# tarjeta-v10.net
KiCad netlist of a schematic drawn in EAGLE
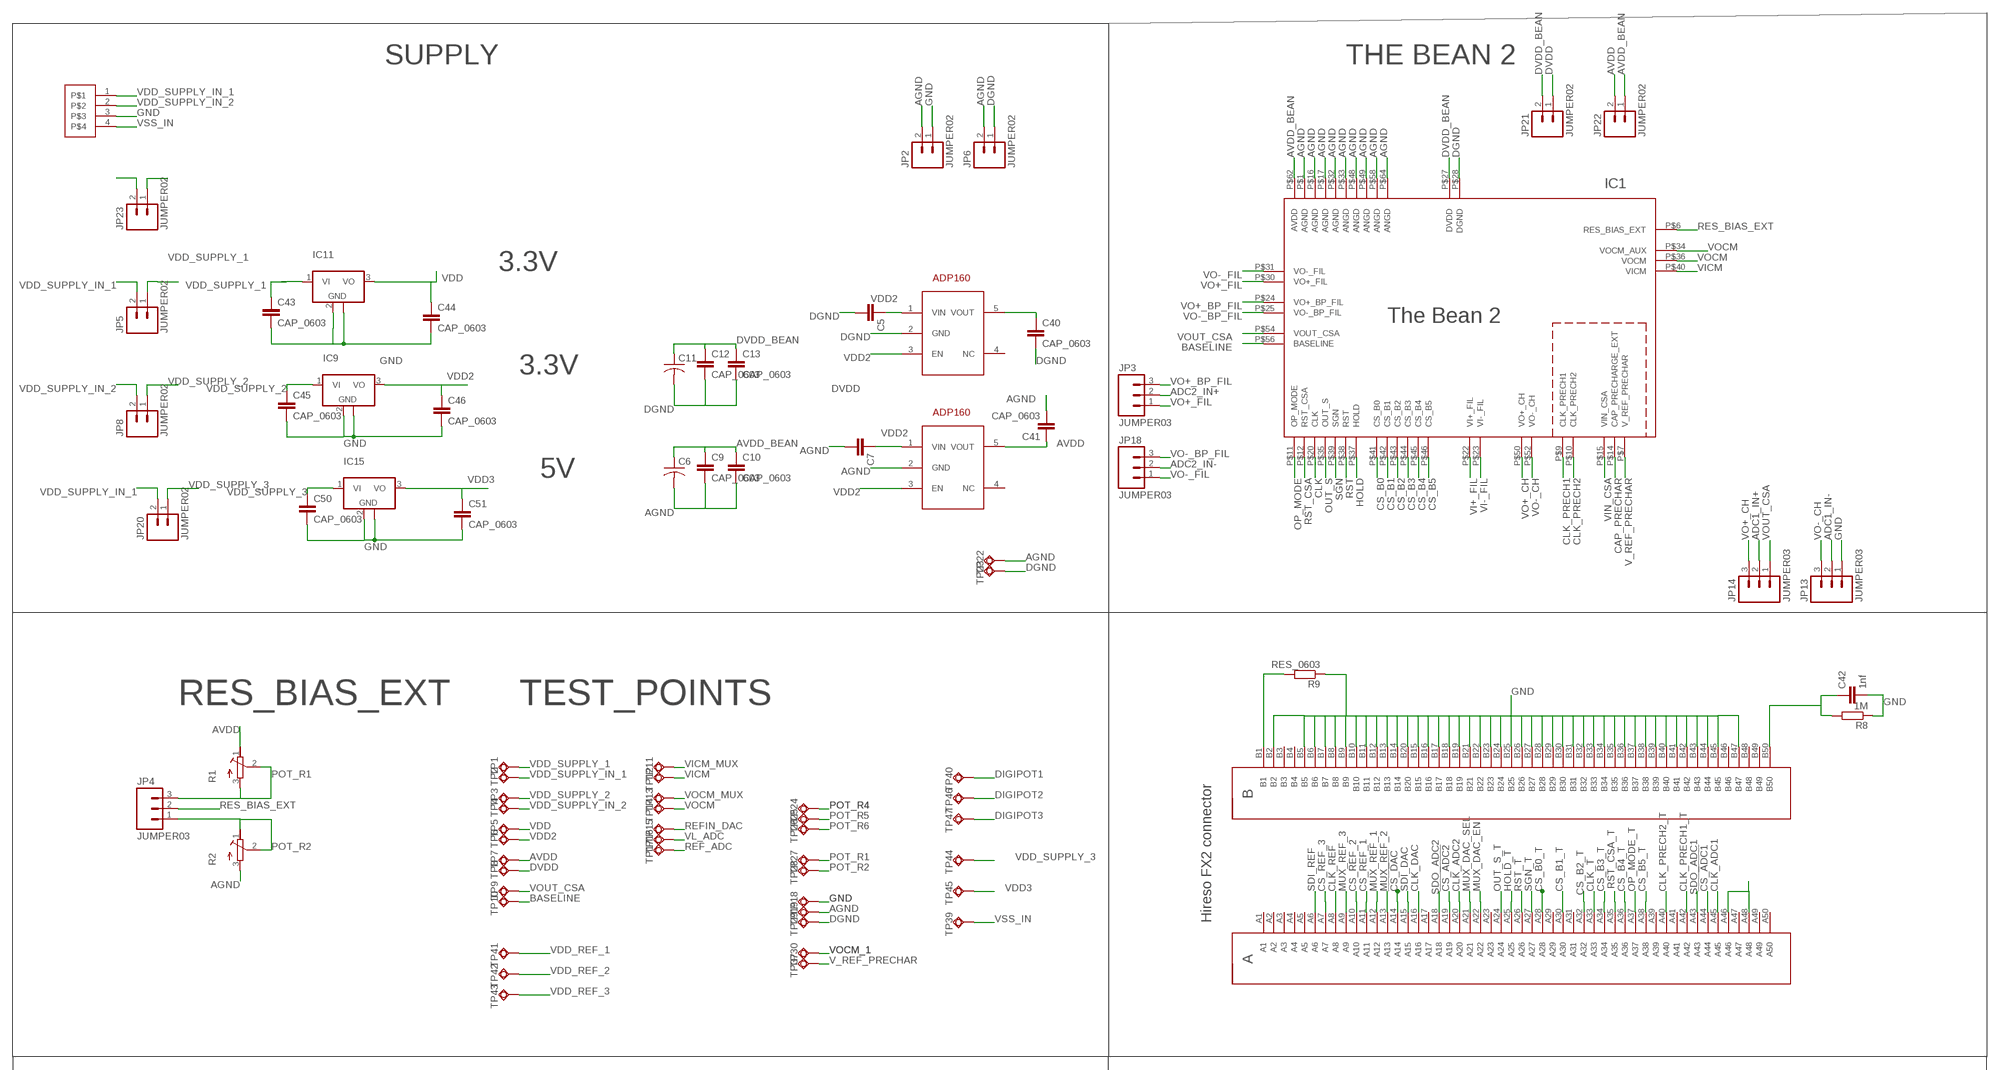
[diagram p0: schematic, sheet 1, part 1 of 3]
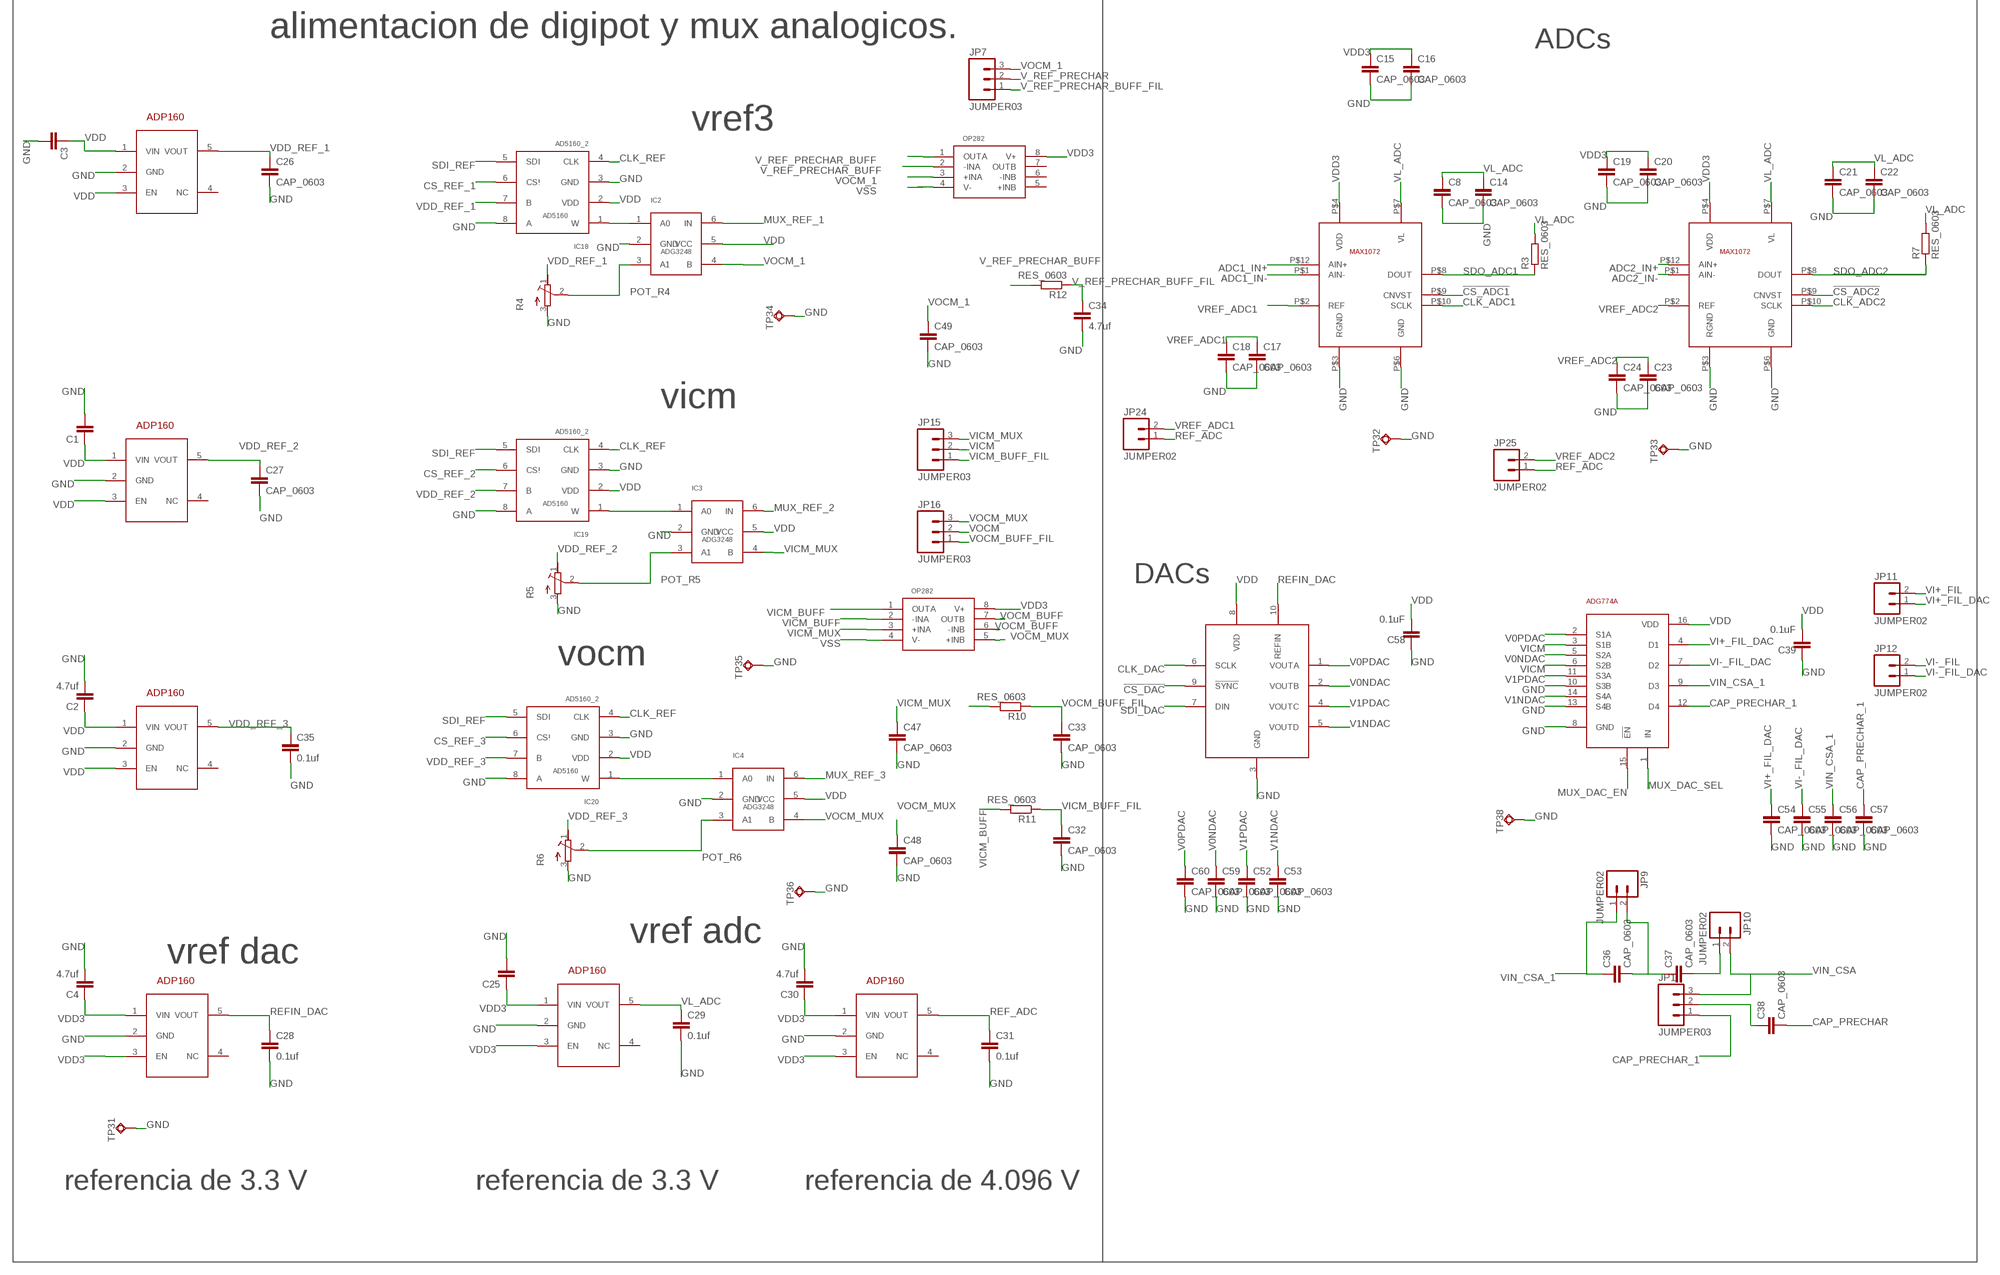
[diagram p1: schematic, sheet 1, part 2 of 3]
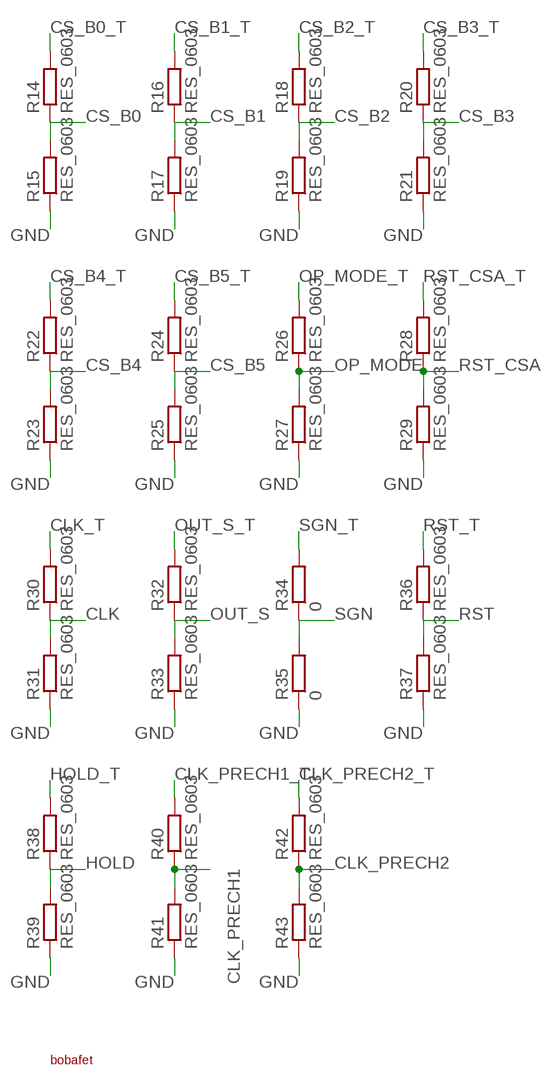
[diagram p2: schematic, sheet 1, part 3 of 3]

(export (version "E")
  (design (tool "Eeschema 10.0.6"))
  (components
    (comp (ref "C1")
      (value "CAP_0402")
      (footprint "eagle-import:C0402")
      (libsource (lib "eagle-import") (part "CAP_0402"))
    )
    (comp (ref "C2")
      (value "4.7uf")
      (footprint "eagle-import:C0402")
      (libsource (lib "eagle-import") (part "CAP_0402"))
    )
    (comp (ref "C3")
      (value "CAP_0402")
      (footprint "eagle-import:C0402")
      (libsource (lib "eagle-import") (part "CAP_0402"))
    )
    (comp (ref "C4")
      (value "4.7uf")
      (footprint "eagle-import:C0402")
      (libsource (lib "eagle-import") (part "CAP_0402"))
    )
    (comp (ref "C5")
      (value "CAP_0402")
      (footprint "eagle-import:C0402")
      (libsource (lib "eagle-import") (part "CAP_0402"))
    )
    (comp (ref "C6")
      (value "CAP_0805")
      (footprint "eagle-import:C0805")
      (libsource (lib "eagle-import") (part "CAP_0805"))
    )
    (comp (ref "C7")
      (value "CAP_0402")
      (footprint "eagle-import:C0402")
      (libsource (lib "eagle-import") (part "CAP_0402"))
    )
    (comp (ref "C8")
      (value "CAP_0603")
      (footprint "eagle-import:C0603")
      (libsource (lib "eagle-import") (part "CAP_0603"))
    )
    (comp (ref "C9")
      (value "CAP_0603")
      (footprint "eagle-import:C0603")
      (libsource (lib "eagle-import") (part "CAP_0603"))
    )
    (comp (ref "C10")
      (value "CAP_0603")
      (footprint "eagle-import:C0603")
      (libsource (lib "eagle-import") (part "CAP_0603"))
    )
    (comp (ref "C11")
      (value "CAP_0805")
      (footprint "eagle-import:C0805")
      (libsource (lib "eagle-import") (part "CAP_0805"))
    )
    (comp (ref "C12")
      (value "CAP_0603")
      (footprint "eagle-import:C0603")
      (libsource (lib "eagle-import") (part "CAP_0603"))
    )
    (comp (ref "C13")
      (value "CAP_0603")
      (footprint "eagle-import:C0603")
      (libsource (lib "eagle-import") (part "CAP_0603"))
    )
    (comp (ref "C14")
      (value "CAP_0603")
      (footprint "eagle-import:C0603")
      (libsource (lib "eagle-import") (part "CAP_0603"))
    )
    (comp (ref "C15")
      (value "CAP_0603")
      (footprint "eagle-import:C0603")
      (libsource (lib "eagle-import") (part "CAP_0603"))
    )
    (comp (ref "C16")
      (value "CAP_0603")
      (footprint "eagle-import:C0603")
      (libsource (lib "eagle-import") (part "CAP_0603"))
    )
    (comp (ref "C17")
      (value "CAP_0603")
      (footprint "eagle-import:C0603")
      (libsource (lib "eagle-import") (part "CAP_0603"))
    )
    (comp (ref "C18")
      (value "CAP_0603")
      (footprint "eagle-import:C0603")
      (libsource (lib "eagle-import") (part "CAP_0603"))
    )
    (comp (ref "C19")
      (value "CAP_0603")
      (footprint "eagle-import:C0603")
      (libsource (lib "eagle-import") (part "CAP_0603"))
    )
    (comp (ref "C20")
      (value "CAP_0603")
      (footprint "eagle-import:C0603")
      (libsource (lib "eagle-import") (part "CAP_0603"))
    )
    (comp (ref "C21")
      (value "CAP_0603")
      (footprint "eagle-import:C0603")
      (libsource (lib "eagle-import") (part "CAP_0603"))
    )
    (comp (ref "C22")
      (value "CAP_0603")
      (footprint "eagle-import:C0603")
      (libsource (lib "eagle-import") (part "CAP_0603"))
    )
    (comp (ref "C23")
      (value "CAP_0603")
      (footprint "eagle-import:C0603")
      (libsource (lib "eagle-import") (part "CAP_0603"))
    )
    (comp (ref "C24")
      (value "CAP_0603")
      (footprint "eagle-import:C0603")
      (libsource (lib "eagle-import") (part "CAP_0603"))
    )
    (comp (ref "C25")
      (value "CAP_0402")
      (footprint "eagle-import:C0402")
      (libsource (lib "eagle-import") (part "CAP_0402"))
    )
    (comp (ref "C26")
      (value "CAP_0603")
      (footprint "eagle-import:C0603")
      (libsource (lib "eagle-import") (part "CAP_0603"))
    )
    (comp (ref "C27")
      (value "CAP_0603")
      (footprint "eagle-import:C0603")
      (libsource (lib "eagle-import") (part "CAP_0603"))
    )
    (comp (ref "C28")
      (value "0.1uf")
      (footprint "eagle-import:C0603")
      (libsource (lib "eagle-import") (part "CAP_0603"))
    )
    (comp (ref "C29")
      (value "0.1uf")
      (footprint "eagle-import:C0603")
      (libsource (lib "eagle-import") (part "CAP_0603"))
    )
    (comp (ref "C30")
      (value "4.7uf")
      (footprint "eagle-import:C0402")
      (libsource (lib "eagle-import") (part "CAP_0402"))
    )
    (comp (ref "C31")
      (value "0.1uf")
      (footprint "eagle-import:C0603")
      (libsource (lib "eagle-import") (part "CAP_0603"))
    )
    (comp (ref "C32")
      (value "CAP_0603")
      (footprint "eagle-import:C0603")
      (libsource (lib "eagle-import") (part "CAP_0603"))
    )
    (comp (ref "C33")
      (value "CAP_0603")
      (footprint "eagle-import:C0603")
      (libsource (lib "eagle-import") (part "CAP_0603"))
    )
    (comp (ref "C34")
      (value "4.7uf")
      (footprint "eagle-import:C0603")
      (libsource (lib "eagle-import") (part "CAP_0603"))
    )
    (comp (ref "C35")
      (value "0.1uf")
      (footprint "eagle-import:C0603")
      (libsource (lib "eagle-import") (part "CAP_0603"))
    )
    (comp (ref "C36")
      (value "CAP_0603")
      (footprint "eagle-import:C0603")
      (libsource (lib "eagle-import") (part "CAP_0603"))
    )
    (comp (ref "C37")
      (value "CAP_0603")
      (footprint "eagle-import:C0603")
      (libsource (lib "eagle-import") (part "CAP_0603"))
    )
    (comp (ref "C38")
      (value "CAP_0603")
      (footprint "eagle-import:C0603")
      (libsource (lib "eagle-import") (part "CAP_0603"))
    )
    (comp (ref "C39")
      (value "0.1uF")
      (footprint "eagle-import:C0603")
      (libsource (lib "eagle-import") (part "CAP_0603"))
    )
    (comp (ref "C40")
      (value "CAP_0603")
      (footprint "eagle-import:C0603")
      (libsource (lib "eagle-import") (part "CAP_0603"))
    )
    (comp (ref "C41")
      (value "CAP_0603")
      (footprint "eagle-import:C0603")
      (libsource (lib "eagle-import") (part "CAP_0603"))
    )
    (comp (ref "C42")
      (value "1nf")
      (footprint "eagle-import:C0603")
      (libsource (lib "eagle-import") (part "CAP_0603"))
    )
    (comp (ref "C43")
      (value "CAP_0603")
      (footprint "eagle-import:C0603")
      (libsource (lib "eagle-import") (part "CAP_0603"))
    )
    (comp (ref "C44")
      (value "CAP_0603")
      (footprint "eagle-import:C0603")
      (libsource (lib "eagle-import") (part "CAP_0603"))
    )
    (comp (ref "C45")
      (value "CAP_0603")
      (footprint "eagle-import:C0603")
      (libsource (lib "eagle-import") (part "CAP_0603"))
    )
    (comp (ref "C46")
      (value "CAP_0603")
      (footprint "eagle-import:C0603")
      (libsource (lib "eagle-import") (part "CAP_0603"))
    )
    (comp (ref "C47")
      (value "CAP_0603")
      (footprint "eagle-import:C0603")
      (libsource (lib "eagle-import") (part "CAP_0603"))
    )
    (comp (ref "C48")
      (value "CAP_0603")
      (footprint "eagle-import:C0603")
      (libsource (lib "eagle-import") (part "CAP_0603"))
    )
    (comp (ref "C49")
      (value "CAP_0603")
      (footprint "eagle-import:C0603")
      (libsource (lib "eagle-import") (part "CAP_0603"))
    )
    (comp (ref "C50")
      (value "CAP_0603")
      (footprint "eagle-import:C0603")
      (libsource (lib "eagle-import") (part "CAP_0603"))
    )
    (comp (ref "C51")
      (value "CAP_0603")
      (footprint "eagle-import:C0603")
      (libsource (lib "eagle-import") (part "CAP_0603"))
    )
    (comp (ref "C52")
      (value "CAP_0603")
      (footprint "eagle-import:C0603")
      (libsource (lib "eagle-import") (part "CAP_0603"))
    )
    (comp (ref "C53")
      (value "CAP_0603")
      (footprint "eagle-import:C0603")
      (libsource (lib "eagle-import") (part "CAP_0603"))
    )
    (comp (ref "C54")
      (value "CAP_0603")
      (footprint "eagle-import:C0603")
      (libsource (lib "eagle-import") (part "CAP_0603"))
    )
    (comp (ref "C55")
      (value "CAP_0603")
      (footprint "eagle-import:C0603")
      (libsource (lib "eagle-import") (part "CAP_0603"))
    )
    (comp (ref "C56")
      (value "CAP_0603")
      (footprint "eagle-import:C0603")
      (libsource (lib "eagle-import") (part "CAP_0603"))
    )
    (comp (ref "C57")
      (value "CAP_0603")
      (footprint "eagle-import:C0603")
      (libsource (lib "eagle-import") (part "CAP_0603"))
    )
    (comp (ref "C58")
      (value "0.1uF")
      (footprint "eagle-import:C0603")
      (libsource (lib "eagle-import") (part "CAP_0603"))
    )
    (comp (ref "C59")
      (value "CAP_0603")
      (footprint "eagle-import:C0603")
      (libsource (lib "eagle-import") (part "CAP_0603"))
    )
    (comp (ref "C60")
      (value "CAP_0603")
      (footprint "eagle-import:C0603")
      (libsource (lib "eagle-import") (part "CAP_0603"))
    )
    (comp (ref "IC1")
      (value "THEBEAN2")
      (footprint "eagle-import:CQFP64")
      (libsource (lib "eagle-import") (part "THEBEAN2"))
    )
    (comp (ref "IC2")
      (value "ADG3248")
      (footprint "eagle-import:SC70")
      (libsource (lib "eagle-import") (part "ADG3248"))
    )
    (comp (ref "IC3")
      (value "ADG3248")
      (footprint "eagle-import:SC70")
      (libsource (lib "eagle-import") (part "ADG3248"))
    )
    (comp (ref "IC4")
      (value "ADG3248")
      (footprint "eagle-import:SC70")
      (libsource (lib "eagle-import") (part "ADG3248"))
    )
    (comp (ref "IC5")
      (value "ADP160")
      (footprint "eagle-import:SOT23-5L_2")
      (libsource (lib "eagle-import") (part "ADP160"))
    )
    (comp (ref "IC6")
      (value "ADP160")
      (footprint "eagle-import:SOT23-5L_2")
      (libsource (lib "eagle-import") (part "ADP160"))
    )
    (comp (ref "IC7")
      (value "ADP160")
      (footprint "eagle-import:SOT23-5L_2")
      (libsource (lib "eagle-import") (part "ADP160"))
    )
    (comp (ref "IC8")
      (value "ADP160")
      (footprint "eagle-import:SOT23-5L_2")
      (libsource (lib "eagle-import") (part "ADP160"))
    )
    (comp (ref "IC9")
      (value "UA78M")
      (footprint "eagle-import:SOT223")
      (libsource (lib "eagle-import") (part "UA78M"))
    )
    (comp (ref "IC10")
      (value "ADP160")
      (footprint "eagle-import:SOT23-5L_2")
      (libsource (lib "eagle-import") (part "ADP160"))
    )
    (comp (ref "IC11")
      (value "UA78M")
      (footprint "eagle-import:SOT223")
      (libsource (lib "eagle-import") (part "UA78M"))
    )
    (comp (ref "IC12")
      (value "OP282")
      (footprint "eagle-import:SOIC8")
      (libsource (lib "eagle-import") (part "OP282"))
    )
    (comp (ref "IC13")
      (value "ADP160")
      (footprint "eagle-import:SOT23-5L_2")
      (libsource (lib "eagle-import") (part "ADP160"))
    )
    (comp (ref "IC14")
      (value "OP282")
      (footprint "eagle-import:SOIC8")
      (libsource (lib "eagle-import") (part "OP282"))
    )
    (comp (ref "IC15")
      (value "UA78M")
      (footprint "eagle-import:SOT223")
      (libsource (lib "eagle-import") (part "UA78M"))
    )
    (comp (ref "IC16")
      (value "ADP160")
      (footprint "eagle-import:SOT23-5L_2")
      (libsource (lib "eagle-import") (part "ADP160"))
    )
    (comp (ref "IC17")
      (value "ADP160")
      (footprint "eagle-import:SOT23-5L_2")
      (libsource (lib "eagle-import") (part "ADP160"))
    )
    (comp (ref "IC18")
      (value "AD5160_2")
      (footprint "eagle-import:SOT23-8_2")
      (libsource (lib "eagle-import") (part "AD5160_2"))
    )
    (comp (ref "IC19")
      (value "AD5160_2")
      (footprint "eagle-import:SOT23-8_2")
      (libsource (lib "eagle-import") (part "AD5160_2"))
    )
    (comp (ref "IC20")
      (value "AD5160_2")
      (footprint "eagle-import:SOT23-8_2")
      (libsource (lib "eagle-import") (part "AD5160_2"))
    )
    (comp (ref "IC21")
      (value "ADG774A")
      (footprint "eagle-import:QSOP16")
      (libsource (lib "eagle-import") (part "ADG774A"))
    )
    (comp (ref "IC22")
      (value "MAX1072")
      (footprint "eagle-import:TQFN12")
      (libsource (lib "eagle-import") (part "MAX1072"))
    )
    (comp (ref "IC23")
      (value "DAC7554")
      (footprint "eagle-import:MSOP10")
      (libsource (lib "eagle-import") (part "DAC7554"))
    )
    (comp (ref "IC24")
      (value "MAX1072")
      (footprint "eagle-import:TQFN12")
      (libsource (lib "eagle-import") (part "MAX1072"))
    )
    (comp (ref "J1")
      (value "HIRESO_FX_CONNECTOR")
      (footprint "eagle-import:FX2-100S-1.27")
      (libsource (lib "eagle-import") (part "HIRESO_FX_CONNECTOR"))
    )
    (comp (ref "JP1")
      (value "JUMPER03")
      (footprint "eagle-import:1X03")
      (libsource (lib "eagle-import") (part "JUMPER03"))
    )
    (comp (ref "JP2")
      (value "JUMPER02")
      (footprint "eagle-import:1X02")
      (libsource (lib "eagle-import") (part "JUMPER02"))
    )
    (comp (ref "JP3")
      (value "JUMPER03")
      (footprint "eagle-import:1X03")
      (libsource (lib "eagle-import") (part "JUMPER03"))
    )
    (comp (ref "JP4")
      (value "JUMPER03")
      (footprint "eagle-import:1X03")
      (libsource (lib "eagle-import") (part "JUMPER03"))
    )
    (comp (ref "JP5")
      (value "JUMPER02")
      (footprint "eagle-import:1X02")
      (libsource (lib "eagle-import") (part "JUMPER02"))
    )
    (comp (ref "JP6")
      (value "JUMPER02")
      (footprint "eagle-import:1X02")
      (libsource (lib "eagle-import") (part "JUMPER02"))
    )
    (comp (ref "JP7")
      (value "JUMPER03")
      (footprint "eagle-import:1X03")
      (libsource (lib "eagle-import") (part "JUMPER03"))
    )
    (comp (ref "JP8")
      (value "JUMPER02")
      (footprint "eagle-import:1X02")
      (libsource (lib "eagle-import") (part "JUMPER02"))
    )
    (comp (ref "JP9")
      (value "JUMPER02")
      (footprint "eagle-import:1X02")
      (libsource (lib "eagle-import") (part "JUMPER02"))
    )
    (comp (ref "JP10")
      (value "JUMPER02")
      (footprint "eagle-import:1X02")
      (libsource (lib "eagle-import") (part "JUMPER02"))
    )
    (comp (ref "JP11")
      (value "JUMPER02")
      (footprint "eagle-import:1X02")
      (libsource (lib "eagle-import") (part "JUMPER02"))
    )
    (comp (ref "JP12")
      (value "JUMPER02")
      (footprint "eagle-import:1X02")
      (libsource (lib "eagle-import") (part "JUMPER02"))
    )
    (comp (ref "JP13")
      (value "JUMPER03")
      (footprint "eagle-import:1X03")
      (libsource (lib "eagle-import") (part "JUMPER03"))
    )
    (comp (ref "JP14")
      (value "JUMPER03")
      (footprint "eagle-import:1X03")
      (libsource (lib "eagle-import") (part "JUMPER03"))
    )
    (comp (ref "JP15")
      (value "JUMPER03")
      (footprint "eagle-import:1X03")
      (libsource (lib "eagle-import") (part "JUMPER03"))
    )
    (comp (ref "JP16")
      (value "JUMPER03")
      (footprint "eagle-import:1X03")
      (libsource (lib "eagle-import") (part "JUMPER03"))
    )
    (comp (ref "JP17")
      (value "JUMPER04")
      (footprint "eagle-import:1X04")
      (libsource (lib "eagle-import") (part "JUMPER04"))
    )
    (comp (ref "JP18")
      (value "JUMPER03")
      (footprint "eagle-import:1X03")
      (libsource (lib "eagle-import") (part "JUMPER03"))
    )
    (comp (ref "JP20")
      (value "JUMPER02")
      (footprint "eagle-import:1X02")
      (libsource (lib "eagle-import") (part "JUMPER02"))
    )
    (comp (ref "JP21")
      (value "JUMPER02")
      (footprint "eagle-import:1X02")
      (libsource (lib "eagle-import") (part "JUMPER02"))
    )
    (comp (ref "JP22")
      (value "JUMPER02")
      (footprint "eagle-import:1X02")
      (libsource (lib "eagle-import") (part "JUMPER02"))
    )
    (comp (ref "JP23")
      (value "JUMPER02")
      (footprint "eagle-import:1X02")
      (libsource (lib "eagle-import") (part "JUMPER02"))
    )
    (comp (ref "JP24")
      (value "JUMPER02")
      (footprint "eagle-import:1X02")
      (libsource (lib "eagle-import") (part "JUMPER02"))
    )
    (comp (ref "JP25")
      (value "JUMPER02")
      (footprint "eagle-import:1X02")
      (libsource (lib "eagle-import") (part "JUMPER02"))
    )
    (comp (ref "R1")
      (value "TRIMMER_ST5")
      (footprint "eagle-import:ST-5EW")
      (libsource (lib "eagle-import") (part "TRIMMER_ST5"))
    )
    (comp (ref "R2")
      (value "TRIMMER_ST5")
      (footprint "eagle-import:ST-5EW")
      (libsource (lib "eagle-import") (part "TRIMMER_ST5"))
    )
    (comp (ref "R3")
      (value "RES_0603")
      (footprint "eagle-import:R0603")
      (libsource (lib "eagle-import") (part "RES_0603"))
    )
    (comp (ref "R4")
      (value "TRIMMER_ST5")
      (footprint "eagle-import:ST-5EW")
      (libsource (lib "eagle-import") (part "TRIMMER_ST5"))
    )
    (comp (ref "R5")
      (value "TRIMMER_ST5")
      (footprint "eagle-import:ST-5EW")
      (libsource (lib "eagle-import") (part "TRIMMER_ST5"))
    )
    (comp (ref "R6")
      (value "TRIMMER_ST5")
      (footprint "eagle-import:ST-5EW")
      (libsource (lib "eagle-import") (part "TRIMMER_ST5"))
    )
    (comp (ref "R7")
      (value "RES_0603")
      (footprint "eagle-import:R0603")
      (libsource (lib "eagle-import") (part "RES_0603"))
    )
    (comp (ref "R8")
      (value "1M")
      (footprint "eagle-import:R0603")
      (libsource (lib "eagle-import") (part "RES_0603"))
    )
    (comp (ref "R9")
      (value "RES_0603")
      (footprint "eagle-import:R0603")
      (libsource (lib "eagle-import") (part "RES_0603"))
    )
    (comp (ref "R10")
      (value "RES_0603")
      (footprint "eagle-import:R0603")
      (libsource (lib "eagle-import") (part "RES_0603"))
    )
    (comp (ref "R11")
      (value "RES_0603")
      (footprint "eagle-import:R0603")
      (libsource (lib "eagle-import") (part "RES_0603"))
    )
    (comp (ref "R12")
      (value "RES_0603")
      (footprint "eagle-import:R0603")
      (libsource (lib "eagle-import") (part "RES_0603"))
    )
    (comp (ref "R14")
      (value "RES_0603")
      (footprint "eagle-import:R0603")
      (libsource (lib "eagle-import") (part "RES_0603"))
    )
    (comp (ref "R15")
      (value "RES_0603")
      (footprint "eagle-import:R0603")
      (libsource (lib "eagle-import") (part "RES_0603"))
    )
    (comp (ref "R16")
      (value "RES_0603")
      (footprint "eagle-import:R0603")
      (libsource (lib "eagle-import") (part "RES_0603"))
    )
    (comp (ref "R17")
      (value "RES_0603")
      (footprint "eagle-import:R0603")
      (libsource (lib "eagle-import") (part "RES_0603"))
    )
    (comp (ref "R18")
      (value "RES_0603")
      (footprint "eagle-import:R0603")
      (libsource (lib "eagle-import") (part "RES_0603"))
    )
    (comp (ref "R19")
      (value "RES_0603")
      (footprint "eagle-import:R0603")
      (libsource (lib "eagle-import") (part "RES_0603"))
    )
    (comp (ref "R20")
      (value "RES_0603")
      (footprint "eagle-import:R0603")
      (libsource (lib "eagle-import") (part "RES_0603"))
    )
    (comp (ref "R21")
      (value "RES_0603")
      (footprint "eagle-import:R0603")
      (libsource (lib "eagle-import") (part "RES_0603"))
    )
    (comp (ref "R22")
      (value "RES_0603")
      (footprint "eagle-import:R0603")
      (libsource (lib "eagle-import") (part "RES_0603"))
    )
    (comp (ref "R23")
      (value "RES_0603")
      (footprint "eagle-import:R0603")
      (libsource (lib "eagle-import") (part "RES_0603"))
    )
    (comp (ref "R24")
      (value "RES_0603")
      (footprint "eagle-import:R0603")
      (libsource (lib "eagle-import") (part "RES_0603"))
    )
    (comp (ref "R25")
      (value "RES_0603")
      (footprint "eagle-import:R0603")
      (libsource (lib "eagle-import") (part "RES_0603"))
    )
    (comp (ref "R26")
      (value "RES_0603")
      (footprint "eagle-import:R0603")
      (libsource (lib "eagle-import") (part "RES_0603"))
    )
    (comp (ref "R27")
      (value "RES_0603")
      (footprint "eagle-import:R0603")
      (libsource (lib "eagle-import") (part "RES_0603"))
    )
    (comp (ref "R28")
      (value "RES_0603")
      (footprint "eagle-import:R0603")
      (libsource (lib "eagle-import") (part "RES_0603"))
    )
    (comp (ref "R29")
      (value "RES_0603")
      (footprint "eagle-import:R0603")
      (libsource (lib "eagle-import") (part "RES_0603"))
    )
    (comp (ref "R30")
      (value "RES_0603")
      (footprint "eagle-import:R0603")
      (libsource (lib "eagle-import") (part "RES_0603"))
    )
    (comp (ref "R31")
      (value "RES_0603")
      (footprint "eagle-import:R0603")
      (libsource (lib "eagle-import") (part "RES_0603"))
    )
    (comp (ref "R32")
      (value "RES_0603")
      (footprint "eagle-import:R0603")
      (libsource (lib "eagle-import") (part "RES_0603"))
    )
    (comp (ref "R33")
      (value "RES_0603")
      (footprint "eagle-import:R0603")
      (libsource (lib "eagle-import") (part "RES_0603"))
    )
    (comp (ref "R34")
      (value "0")
      (footprint "eagle-import:R0603")
      (libsource (lib "eagle-import") (part "RES_0603"))
    )
    (comp (ref "R35")
      (value "0")
      (footprint "eagle-import:R0603")
      (libsource (lib "eagle-import") (part "RES_0603"))
    )
    (comp (ref "R36")
      (value "RES_0603")
      (footprint "eagle-import:R0603")
      (libsource (lib "eagle-import") (part "RES_0603"))
    )
    (comp (ref "R37")
      (value "RES_0603")
      (footprint "eagle-import:R0603")
      (libsource (lib "eagle-import") (part "RES_0603"))
    )
    (comp (ref "R38")
      (value "RES_0603")
      (footprint "eagle-import:R0603")
      (libsource (lib "eagle-import") (part "RES_0603"))
    )
    (comp (ref "R39")
      (value "RES_0603")
      (footprint "eagle-import:R0603")
      (libsource (lib "eagle-import") (part "RES_0603"))
    )
    (comp (ref "R40")
      (value "RES_0603")
      (footprint "eagle-import:R0603")
      (libsource (lib "eagle-import") (part "RES_0603"))
    )
    (comp (ref "R41")
      (value "RES_0603")
      (footprint "eagle-import:R0603")
      (libsource (lib "eagle-import") (part "RES_0603"))
    )
    (comp (ref "R42")
      (value "RES_0603")
      (footprint "eagle-import:R0603")
      (libsource (lib "eagle-import") (part "RES_0603"))
    )
    (comp (ref "R43")
      (value "RES_0603")
      (footprint "eagle-import:R0603")
      (libsource (lib "eagle-import") (part "RES_0603"))
    )
    (comp (ref "TP1")
      (value "TEST_POINT")
      (footprint "eagle-import:TP")
      (libsource (lib "eagle-import") (part "TEST_POINT"))
    )
    (comp (ref "TP2")
      (value "TEST_POINT")
      (footprint "eagle-import:TP")
      (libsource (lib "eagle-import") (part "TEST_POINT"))
    )
    (comp (ref "TP3")
      (value "TEST_POINT")
      (footprint "eagle-import:TP")
      (libsource (lib "eagle-import") (part "TEST_POINT"))
    )
    (comp (ref "TP4")
      (value "TEST_POINT")
      (footprint "eagle-import:TP")
      (libsource (lib "eagle-import") (part "TEST_POINT"))
    )
    (comp (ref "TP5")
      (value "TEST_POINT")
      (footprint "eagle-import:TP")
      (libsource (lib "eagle-import") (part "TEST_POINT"))
    )
    (comp (ref "TP6")
      (value "TEST_POINT")
      (footprint "eagle-import:TP")
      (libsource (lib "eagle-import") (part "TEST_POINT"))
    )
    (comp (ref "TP7")
      (value "TEST_POINT")
      (footprint "eagle-import:TP")
      (libsource (lib "eagle-import") (part "TEST_POINT"))
    )
    (comp (ref "TP8")
      (value "TEST_POINT")
      (footprint "eagle-import:TP")
      (libsource (lib "eagle-import") (part "TEST_POINT"))
    )
    (comp (ref "TP9")
      (value "TEST_POINT")
      (footprint "eagle-import:TP")
      (libsource (lib "eagle-import") (part "TEST_POINT"))
    )
    (comp (ref "TP10")
      (value "TEST_POINT")
      (footprint "eagle-import:TP")
      (libsource (lib "eagle-import") (part "TEST_POINT"))
    )
    (comp (ref "TP11")
      (value "TEST_POINT")
      (footprint "eagle-import:TP")
      (libsource (lib "eagle-import") (part "TEST_POINT"))
    )
    (comp (ref "TP12")
      (value "TEST_POINT")
      (footprint "eagle-import:TP")
      (libsource (lib "eagle-import") (part "TEST_POINT"))
    )
    (comp (ref "TP13")
      (value "TEST_POINT")
      (footprint "eagle-import:TP")
      (libsource (lib "eagle-import") (part "TEST_POINT"))
    )
    (comp (ref "TP14")
      (value "TEST_POINT")
      (footprint "eagle-import:TP")
      (libsource (lib "eagle-import") (part "TEST_POINT"))
    )
    (comp (ref "TP15")
      (value "TEST_POINT")
      (footprint "eagle-import:TP")
      (libsource (lib "eagle-import") (part "TEST_POINT"))
    )
    (comp (ref "TP16")
      (value "TEST_POINT")
      (footprint "eagle-import:TP")
      (libsource (lib "eagle-import") (part "TEST_POINT"))
    )
    (comp (ref "TP17")
      (value "TEST_POINT")
      (footprint "eagle-import:TP")
      (libsource (lib "eagle-import") (part "TEST_POINT"))
    )
    (comp (ref "TP18")
      (value "TEST_POINT")
      (footprint "eagle-import:TP")
      (libsource (lib "eagle-import") (part "TEST_POINT"))
    )
    (comp (ref "TP19")
      (value "TEST_POINT")
      (footprint "eagle-import:TP")
      (libsource (lib "eagle-import") (part "TEST_POINT"))
    )
    (comp (ref "TP22")
      (value "TEST_POINT")
      (footprint "eagle-import:TP")
      (libsource (lib "eagle-import") (part "TEST_POINT"))
    )
    (comp (ref "TP23")
      (value "TEST_POINT")
      (footprint "eagle-import:TP")
      (libsource (lib "eagle-import") (part "TEST_POINT"))
    )
    (comp (ref "TP24")
      (value "TEST_POINT")
      (footprint "eagle-import:TP")
      (libsource (lib "eagle-import") (part "TEST_POINT"))
    )
    (comp (ref "TP25")
      (value "TEST_POINT")
      (footprint "eagle-import:TP")
      (libsource (lib "eagle-import") (part "TEST_POINT"))
    )
    (comp (ref "TP26")
      (value "TEST_POINT")
      (footprint "eagle-import:TP")
      (libsource (lib "eagle-import") (part "TEST_POINT"))
    )
    (comp (ref "TP27")
      (value "TEST_POINT")
      (footprint "eagle-import:TP")
      (libsource (lib "eagle-import") (part "TEST_POINT"))
    )
    (comp (ref "TP28")
      (value "TEST_POINT")
      (footprint "eagle-import:TP")
      (libsource (lib "eagle-import") (part "TEST_POINT"))
    )
    (comp (ref "TP29")
      (value "TEST_POINT")
      (footprint "eagle-import:TP")
      (libsource (lib "eagle-import") (part "TEST_POINT"))
    )
    (comp (ref "TP30")
      (value "TEST_POINT")
      (footprint "eagle-import:TP")
      (libsource (lib "eagle-import") (part "TEST_POINT"))
    )
    (comp (ref "TP31")
      (value "TEST_POINT")
      (footprint "eagle-import:TP")
      (libsource (lib "eagle-import") (part "TEST_POINT"))
    )
    (comp (ref "TP32")
      (value "TEST_POINT")
      (footprint "eagle-import:TP")
      (libsource (lib "eagle-import") (part "TEST_POINT"))
    )
    (comp (ref "TP33")
      (value "TEST_POINT")
      (footprint "eagle-import:TP")
      (libsource (lib "eagle-import") (part "TEST_POINT"))
    )
    (comp (ref "TP34")
      (value "TEST_POINT")
      (footprint "eagle-import:TP")
      (libsource (lib "eagle-import") (part "TEST_POINT"))
    )
    (comp (ref "TP35")
      (value "TEST_POINT")
      (footprint "eagle-import:TP")
      (libsource (lib "eagle-import") (part "TEST_POINT"))
    )
    (comp (ref "TP36")
      (value "TEST_POINT")
      (footprint "eagle-import:TP")
      (libsource (lib "eagle-import") (part "TEST_POINT"))
    )
    (comp (ref "TP37")
      (value "TEST_POINT")
      (footprint "eagle-import:TP")
      (libsource (lib "eagle-import") (part "TEST_POINT"))
    )
    (comp (ref "TP38")
      (value "TEST_POINT")
      (footprint "eagle-import:TP")
      (libsource (lib "eagle-import") (part "TEST_POINT"))
    )
    (comp (ref "TP39")
      (value "TEST_POINT")
      (footprint "eagle-import:TP")
      (libsource (lib "eagle-import") (part "TEST_POINT"))
    )
    (comp (ref "TP40")
      (value "TEST_POINT")
      (footprint "eagle-import:TP")
      (libsource (lib "eagle-import") (part "TEST_POINT"))
    )
    (comp (ref "TP41")
      (value "TEST_POINT")
      (footprint "eagle-import:TP")
      (libsource (lib "eagle-import") (part "TEST_POINT"))
    )
    (comp (ref "TP42")
      (value "TEST_POINT")
      (footprint "eagle-import:TP")
      (libsource (lib "eagle-import") (part "TEST_POINT"))
    )
    (comp (ref "TP43")
      (value "TEST_POINT")
      (footprint "eagle-import:TP")
      (libsource (lib "eagle-import") (part "TEST_POINT"))
    )
    (comp (ref "TP44")
      (value "TEST_POINT")
      (footprint "eagle-import:TP")
      (libsource (lib "eagle-import") (part "TEST_POINT"))
    )
    (comp (ref "TP45")
      (value "TEST_POINT")
      (footprint "eagle-import:TP")
      (libsource (lib "eagle-import") (part "TEST_POINT"))
    )
    (comp (ref "TP46")
      (value "TEST_POINT")
      (footprint "eagle-import:TP")
      (libsource (lib "eagle-import") (part "TEST_POINT"))
    )
    (comp (ref "TP47")
      (value "TEST_POINT")
      (footprint "eagle-import:TP")
      (libsource (lib "eagle-import") (part "TEST_POINT"))
    )
    (comp (ref "U$1")
      (value "LOGO")
      (footprint "eagle-import:LOGO")
      (libsource (lib "eagle-import") (part "LOGO"))
    )
  )
  (nets
    (net (code "1") (name "/ADC1_IN+") (class "Default")
      (node (ref "IC22") (pin "P$12") (pinfunction "AIN+_P$12") (pintype "bidirectional"))
      (node (ref "JP14") (pin "2") (pinfunction "2_2") (pintype "passive"))
    )
    (net (code "2") (name "/ADC1_IN-") (class "Default")
      (node (ref "IC22") (pin "P$1") (pinfunction "AIN-_P$1") (pintype "bidirectional"))
      (node (ref "JP13") (pin "2") (pinfunction "2_2") (pintype "passive"))
    )
    (net (code "3") (name "/ADC2_IN+") (class "Default")
      (node (ref "IC24") (pin "P$12") (pinfunction "AIN+_P$12") (pintype "bidirectional"))
      (node (ref "JP3") (pin "2") (pinfunction "2_2") (pintype "passive"))
    )
    (net (code "4") (name "/ADC2_IN-") (class "Default")
      (node (ref "IC24") (pin "P$1") (pinfunction "AIN-_P$1") (pintype "bidirectional"))
      (node (ref "JP18") (pin "2") (pinfunction "2_2") (pintype "passive"))
    )
    (net (code "5") (name "/AGND") (class "Default")
      (node (ref "C10") (pin "2") (pinfunction "2_2") (pintype "passive"))
      (node (ref "C41") (pin "2") (pinfunction "2_2") (pintype "passive"))
      (node (ref "C6") (pin "2") (pinfunction "2_2") (pintype "passive"))
      (node (ref "C7") (pin "2") (pinfunction "2_2") (pintype "passive"))
      (node (ref "C9") (pin "2") (pinfunction "2_2") (pintype "passive"))
      (node (ref "IC1") (pin "P$1") (pinfunction "AGND_P$1") (pintype "power_in"))
      (node (ref "IC1") (pin "P$16") (pinfunction "AGND_P$16") (pintype "power_in"))
      (node (ref "IC1") (pin "P$17") (pinfunction "AGND_P$17") (pintype "power_in"))
      (node (ref "IC1") (pin "P$32") (pinfunction "AGND_P$32") (pintype "power_in"))
      (node (ref "IC1") (pin "P$33") (pinfunction "ANGD_P$33") (pintype "power_in"))
      (node (ref "IC1") (pin "P$48") (pinfunction "ANGD_P$48") (pintype "power_in"))
      (node (ref "IC1") (pin "P$49") (pinfunction "ANGD_P$49") (pintype "power_in"))
      (node (ref "IC1") (pin "P$58") (pinfunction "ANGD_P$58") (pintype "power_in"))
      (node (ref "IC1") (pin "P$64") (pinfunction "ANGD_P$64") (pintype "power_in"))
      (node (ref "IC13") (pin "2") (pinfunction "GND_2") (pintype "bidirectional"))
      (node (ref "JP2") (pin "2") (pinfunction "2_2") (pintype "passive"))
      (node (ref "JP6") (pin "2") (pinfunction "2_2") (pintype "passive"))
      (node (ref "R2") (pin "3") (pinfunction "3_3") (pintype "passive"))
      (node (ref "TP19") (pin "TP") (pinfunction "TP_TP") (pintype "input"))
      (node (ref "TP22") (pin "TP") (pinfunction "TP_TP") (pintype "input"))
    )
    (net (code "6") (name "/AVDD") (class "Default")
      (node (ref "C41") (pin "1") (pinfunction "1_1") (pintype "passive"))
      (node (ref "IC13") (pin "5") (pinfunction "VOUT_5") (pintype "bidirectional"))
      (node (ref "JP22") (pin "2") (pinfunction "2_2") (pintype "passive"))
      (node (ref "R1") (pin "1") (pinfunction "1_1") (pintype "passive"))
      (node (ref "TP7") (pin "TP") (pinfunction "TP_TP") (pintype "input"))
    )
    (net (code "7") (name "/AVDD_BEAN") (class "Default")
      (node (ref "C10") (pin "1") (pinfunction "1_1") (pintype "passive"))
      (node (ref "C6") (pin "1") (pinfunction "1_1") (pintype "passive"))
      (node (ref "C9") (pin "1") (pinfunction "1_1") (pintype "passive"))
      (node (ref "IC1") (pin "P$62") (pinfunction "AVDD_P$62") (pintype "power_in"))
      (node (ref "JP22") (pin "1") (pinfunction "1_1") (pintype "passive"))
    )
    (net (code "8") (name "/BASELINE") (class "Default")
      (node (ref "IC1") (pin "P$56") (pinfunction "BASELINE_P$56") (pintype "output"))
      (node (ref "TP10") (pin "TP") (pinfunction "TP_TP") (pintype "input"))
    )
    (net (code "9") (name "/CAP_PRECHAR") (class "Default")
      (node (ref "C38") (pin "2") (pinfunction "2_2") (pintype "passive"))
      (node (ref "IC1") (pin "P$14") (pinfunction "CAP_PRECHARGE_EXT_P$14") (pintype "input"))
    )
    (net (code "10") (name "/CAP_PRECHAR_1") (class "Default")
      (node (ref "C57") (pin "1") (pinfunction "1_1") (pintype "passive"))
      (node (ref "IC21") (pin "12") (pinfunction "D4_12") (pintype "bidirectional"))
      (node (ref "JP1") (pin "1") (pinfunction "1_1") (pintype "passive"))
    )
    (net (code "11") (name "/CLK") (class "Default")
      (node (ref "IC1") (pin "P$20") (pinfunction "CLK_P$20") (pintype "bidirectional"))
      (node (ref "R30") (pin "1") (pinfunction "1_1") (pintype "passive"))
      (node (ref "R31") (pin "2") (pinfunction "2_2") (pintype "passive"))
    )
    (net (code "12") (name "/CLK_ADC1") (class "Default")
      (node (ref "IC22") (pin "P$10") (pinfunction "SCLK_P$10") (pintype "bidirectional"))
      (node (ref "J1") (pin "A45") (pinfunction "A45_A45") (pintype "bidirectional"))
    )
    (net (code "13") (name "/CLK_ADC2") (class "Default")
      (node (ref "IC24") (pin "P$10") (pinfunction "SCLK_P$10") (pintype "bidirectional"))
      (node (ref "J1") (pin "A20") (pinfunction "A20_A20") (pintype "bidirectional"))
    )
    (net (code "14") (name "/CLK_DAC") (class "Default")
      (node (ref "IC23") (pin "6") (pinfunction "SCLK_6") (pintype "bidirectional"))
      (node (ref "J1") (pin "A16") (pinfunction "A16_A16") (pintype "bidirectional"))
    )
    (net (code "15") (name "/CLK_PRECH1") (class "Default")
      (node (ref "IC1") (pin "P$9") (pinfunction "CLK_PRECH1_P$9") (pintype "bidirectional"))
      (node (ref "R40") (pin "1") (pinfunction "1_1") (pintype "passive"))
      (node (ref "R41") (pin "2") (pinfunction "2_2") (pintype "passive"))
    )
    (net (code "16") (name "/CLK_PRECH1_T") (class "Default")
      (node (ref "J1") (pin "A42") (pinfunction "A42_A42") (pintype "bidirectional"))
      (node (ref "R40") (pin "2") (pinfunction "2_2") (pintype "passive"))
    )
    (net (code "17") (name "/CLK_PRECH2") (class "Default")
      (node (ref "IC1") (pin "P$10") (pinfunction "CLK_PRECH2_P$10") (pintype "bidirectional"))
      (node (ref "R42") (pin "1") (pinfunction "1_1") (pintype "passive"))
      (node (ref "R43") (pin "2") (pinfunction "2_2") (pintype "passive"))
    )
    (net (code "18") (name "/CLK_PRECH2_T") (class "Default")
      (node (ref "J1") (pin "A40") (pinfunction "A40_A40") (pintype "bidirectional"))
      (node (ref "R42") (pin "2") (pinfunction "2_2") (pintype "passive"))
    )
    (net (code "19") (name "/CLK_REF") (class "Default")
      (node (ref "IC18") (pin "4") (pinfunction "CLK_4") (pintype "bidirectional"))
      (node (ref "IC19") (pin "4") (pinfunction "CLK_4") (pintype "bidirectional"))
      (node (ref "IC20") (pin "4") (pinfunction "CLK_4") (pintype "bidirectional"))
      (node (ref "J1") (pin "A8") (pinfunction "A8_A8") (pintype "bidirectional"))
    )
    (net (code "20") (name "/CLK_T") (class "Default")
      (node (ref "J1") (pin "A33") (pinfunction "A33_A33") (pintype "bidirectional"))
      (node (ref "R30") (pin "2") (pinfunction "2_2") (pintype "passive"))
    )
    (net (code "21") (name "/CS_B0") (class "Default")
      (node (ref "IC1") (pin "P$41") (pinfunction "CS_B0_P$41") (pintype "bidirectional"))
      (node (ref "R14") (pin "1") (pinfunction "1_1") (pintype "passive"))
      (node (ref "R15") (pin "2") (pinfunction "2_2") (pintype "passive"))
    )
    (net (code "22") (name "/CS_B0_T") (class "Default")
      (node (ref "J1") (pin "A28") (pinfunction "A28_A28") (pintype "bidirectional"))
      (node (ref "R14") (pin "2") (pinfunction "2_2") (pintype "passive"))
    )
    (net (code "23") (name "/CS_B1") (class "Default")
      (node (ref "IC1") (pin "P$42") (pinfunction "CS_B1_P$42") (pintype "bidirectional"))
      (node (ref "R16") (pin "1") (pinfunction "1_1") (pintype "passive"))
      (node (ref "R17") (pin "2") (pinfunction "2_2") (pintype "passive"))
    )
    (net (code "24") (name "/CS_B1_T") (class "Default")
      (node (ref "J1") (pin "A30") (pinfunction "A30_A30") (pintype "bidirectional"))
      (node (ref "R16") (pin "2") (pinfunction "2_2") (pintype "passive"))
    )
    (net (code "25") (name "/CS_B2") (class "Default")
      (node (ref "IC1") (pin "P$43") (pinfunction "CS_B2_P$43") (pintype "bidirectional"))
      (node (ref "R18") (pin "1") (pinfunction "1_1") (pintype "passive"))
      (node (ref "R19") (pin "2") (pinfunction "2_2") (pintype "passive"))
    )
    (net (code "26") (name "/CS_B2_T") (class "Default")
      (node (ref "J1") (pin "A32") (pinfunction "A32_A32") (pintype "bidirectional"))
      (node (ref "R18") (pin "2") (pinfunction "2_2") (pintype "passive"))
    )
    (net (code "27") (name "/CS_B3") (class "Default")
      (node (ref "IC1") (pin "P$44") (pinfunction "CS_B3_P$44") (pintype "bidirectional"))
      (node (ref "R20") (pin "1") (pinfunction "1_1") (pintype "passive"))
      (node (ref "R21") (pin "2") (pinfunction "2_2") (pintype "passive"))
    )
    (net (code "28") (name "/CS_B3_T") (class "Default")
      (node (ref "J1") (pin "A34") (pinfunction "A34_A34") (pintype "bidirectional"))
      (node (ref "R20") (pin "2") (pinfunction "2_2") (pintype "passive"))
    )
    (net (code "29") (name "/CS_B4") (class "Default")
      (node (ref "IC1") (pin "P$45") (pinfunction "CS_B4_P$45") (pintype "bidirectional"))
      (node (ref "R22") (pin "1") (pinfunction "1_1") (pintype "passive"))
      (node (ref "R23") (pin "2") (pinfunction "2_2") (pintype "passive"))
    )
    (net (code "30") (name "/CS_B4_T") (class "Default")
      (node (ref "J1") (pin "A36") (pinfunction "A36_A36") (pintype "bidirectional"))
      (node (ref "R22") (pin "2") (pinfunction "2_2") (pintype "passive"))
    )
    (net (code "31") (name "/CS_B5") (class "Default")
      (node (ref "IC1") (pin "P$46") (pinfunction "CS_B5_P$46") (pintype "bidirectional"))
      (node (ref "R24") (pin "1") (pinfunction "1_1") (pintype "passive"))
      (node (ref "R25") (pin "2") (pinfunction "2_2") (pintype "passive"))
    )
    (net (code "32") (name "/CS_B5_T") (class "Default")
      (node (ref "J1") (pin "A38") (pinfunction "A38_A38") (pintype "bidirectional"))
      (node (ref "R24") (pin "2") (pinfunction "2_2") (pintype "passive"))
    )
    (net (code "33") (name "/CS_REF_1") (class "Default")
      (node (ref "IC18") (pin "6") (pinfunction "CS~{}_6") (pintype "bidirectional"))
      (node (ref "J1") (pin "A11") (pinfunction "A11_A11") (pintype "bidirectional"))
    )
    (net (code "34") (name "/CS_REF_2") (class "Default")
      (node (ref "IC19") (pin "6") (pinfunction "CS~{}_6") (pintype "bidirectional"))
      (node (ref "J1") (pin "A10") (pinfunction "A10_A10") (pintype "bidirectional"))
    )
    (net (code "35") (name "/CS_REF_3") (class "Default")
      (node (ref "IC20") (pin "6") (pinfunction "CS~{}_6") (pintype "bidirectional"))
      (node (ref "J1") (pin "A7") (pinfunction "A7_A7") (pintype "bidirectional"))
    )
    (net (code "36") (name "/DGND") (class "Default")
      (node (ref "C11") (pin "2") (pinfunction "2_2") (pintype "passive"))
      (node (ref "C12") (pin "2") (pinfunction "2_2") (pintype "passive"))
      (node (ref "C13") (pin "2") (pinfunction "2_2") (pintype "passive"))
      (node (ref "C40") (pin "2") (pinfunction "2_2") (pintype "passive"))
      (node (ref "C5") (pin "2") (pinfunction "2_2") (pintype "passive"))
      (node (ref "IC1") (pin "P$28") (pinfunction "DGND_P$28") (pintype "power_in"))
      (node (ref "IC10") (pin "2") (pinfunction "GND_2") (pintype "bidirectional"))
      (node (ref "JP6") (pin "1") (pinfunction "1_1") (pintype "passive"))
      (node (ref "TP23") (pin "TP") (pinfunction "TP_TP") (pintype "input"))
      (node (ref "TP29") (pin "TP") (pinfunction "TP_TP") (pintype "input"))
    )
    (net (code "37") (name "/DIGIPOT1") (class "Default")
      (node (ref "IC18") (pin "1") (pinfunction "W_1") (pintype "bidirectional"))
      (node (ref "IC2") (pin "1") (pinfunction "A0_1") (pintype "bidirectional"))
      (node (ref "TP40") (pin "TP") (pinfunction "TP_TP") (pintype "input"))
    )
    (net (code "38") (name "/DIGIPOT2") (class "Default")
      (node (ref "IC19") (pin "1") (pinfunction "W_1") (pintype "bidirectional"))
      (node (ref "IC3") (pin "1") (pinfunction "A0_1") (pintype "bidirectional"))
      (node (ref "TP46") (pin "TP") (pinfunction "TP_TP") (pintype "input"))
    )
    (net (code "39") (name "/DIGIPOT3") (class "Default")
      (node (ref "IC20") (pin "1") (pinfunction "W_1") (pintype "bidirectional"))
      (node (ref "IC4") (pin "1") (pinfunction "A0_1") (pintype "bidirectional"))
      (node (ref "TP47") (pin "TP") (pinfunction "TP_TP") (pintype "input"))
    )
    (net (code "40") (name "/DVDD") (class "Default")
      (node (ref "C40") (pin "1") (pinfunction "1_1") (pintype "passive"))
      (node (ref "IC10") (pin "5") (pinfunction "VOUT_5") (pintype "bidirectional"))
      (node (ref "JP21") (pin "1") (pinfunction "1_1") (pintype "passive"))
      (node (ref "TP8") (pin "TP") (pinfunction "TP_TP") (pintype "input"))
    )
    (net (code "41") (name "/DVDD_BEAN") (class "Default")
      (node (ref "C11") (pin "1") (pinfunction "1_1") (pintype "passive"))
      (node (ref "C12") (pin "1") (pinfunction "1_1") (pintype "passive"))
      (node (ref "C13") (pin "1") (pinfunction "1_1") (pintype "passive"))
      (node (ref "IC1") (pin "P$27") (pinfunction "DVDD_P$27") (pintype "power_in"))
      (node (ref "JP21") (pin "2") (pinfunction "2_2") (pintype "passive"))
    )
    (net (code "42") (name "/GND") (class "Default")
      (node (ref "C1") (pin "2") (pinfunction "2_2") (pintype "passive"))
      (node (ref "C14") (pin "2") (pinfunction "2_2") (pintype "passive"))
      (node (ref "C15") (pin "2") (pinfunction "2_2") (pintype "passive"))
      (node (ref "C16") (pin "2") (pinfunction "2_2") (pintype "passive"))
      (node (ref "C17") (pin "2") (pinfunction "2_2") (pintype "passive"))
      (node (ref "C18") (pin "2") (pinfunction "2_2") (pintype "passive"))
      (node (ref "C19") (pin "2") (pinfunction "2_2") (pintype "passive"))
      (node (ref "C2") (pin "2") (pinfunction "2_2") (pintype "passive"))
      (node (ref "C20") (pin "2") (pinfunction "2_2") (pintype "passive"))
      (node (ref "C21") (pin "2") (pinfunction "2_2") (pintype "passive"))
      (node (ref "C22") (pin "2") (pinfunction "2_2") (pintype "passive"))
      (node (ref "C23") (pin "2") (pinfunction "2_2") (pintype "passive"))
      (node (ref "C24") (pin "2") (pinfunction "2_2") (pintype "passive"))
      (node (ref "C25") (pin "2") (pinfunction "2_2") (pintype "passive"))
      (node (ref "C26") (pin "2") (pinfunction "2_2") (pintype "passive"))
      (node (ref "C27") (pin "2") (pinfunction "2_2") (pintype "passive"))
      (node (ref "C28") (pin "2") (pinfunction "2_2") (pintype "passive"))
      (node (ref "C29") (pin "2") (pinfunction "2_2") (pintype "passive"))
      (node (ref "C3") (pin "2") (pinfunction "2_2") (pintype "passive"))
      (node (ref "C30") (pin "2") (pinfunction "2_2") (pintype "passive"))
      (node (ref "C31") (pin "2") (pinfunction "2_2") (pintype "passive"))
      (node (ref "C32") (pin "2") (pinfunction "2_2") (pintype "passive"))
      (node (ref "C33") (pin "2") (pinfunction "2_2") (pintype "passive"))
      (node (ref "C34") (pin "2") (pinfunction "2_2") (pintype "passive"))
      (node (ref "C35") (pin "2") (pinfunction "2_2") (pintype "passive"))
      (node (ref "C39") (pin "1") (pinfunction "1_1") (pintype "passive"))
      (node (ref "C4") (pin "2") (pinfunction "2_2") (pintype "passive"))
      (node (ref "C42") (pin "2") (pinfunction "2_2") (pintype "passive"))
      (node (ref "C43") (pin "2") (pinfunction "2_2") (pintype "passive"))
      (node (ref "C44") (pin "2") (pinfunction "2_2") (pintype "passive"))
      (node (ref "C45") (pin "2") (pinfunction "2_2") (pintype "passive"))
      (node (ref "C46") (pin "2") (pinfunction "2_2") (pintype "passive"))
      (node (ref "C47") (pin "2") (pinfunction "2_2") (pintype "passive"))
      (node (ref "C48") (pin "2") (pinfunction "2_2") (pintype "passive"))
      (node (ref "C49") (pin "2") (pinfunction "2_2") (pintype "passive"))
      (node (ref "C50") (pin "2") (pinfunction "2_2") (pintype "passive"))
      (node (ref "C51") (pin "2") (pinfunction "2_2") (pintype "passive"))
      (node (ref "C52") (pin "2") (pinfunction "2_2") (pintype "passive"))
      (node (ref "C53") (pin "2") (pinfunction "2_2") (pintype "passive"))
      (node (ref "C54") (pin "2") (pinfunction "2_2") (pintype "passive"))
      (node (ref "C55") (pin "2") (pinfunction "2_2") (pintype "passive"))
      (node (ref "C56") (pin "2") (pinfunction "2_2") (pintype "passive"))
      (node (ref "C57") (pin "2") (pinfunction "2_2") (pintype "passive"))
      (node (ref "C58") (pin "1") (pinfunction "1_1") (pintype "passive"))
      (node (ref "C59") (pin "2") (pinfunction "2_2") (pintype "passive"))
      (node (ref "C60") (pin "2") (pinfunction "2_2") (pintype "passive"))
      (node (ref "C8") (pin "2") (pinfunction "2_2") (pintype "passive"))
      (node (ref "IC11") (pin "2") (pinfunction "GND_2") (pintype "passive"))
      (node (ref "IC11") (pin "4") (pinfunction "GND_4") (pintype "passive"))
      (node (ref "IC15") (pin "2") (pinfunction "GND_2") (pintype "passive"))
      (node (ref "IC15") (pin "4") (pinfunction "GND_4") (pintype "passive"))
      (node (ref "IC16") (pin "2") (pinfunction "GND_2") (pintype "bidirectional"))
      (node (ref "IC17") (pin "2") (pinfunction "GND_2") (pintype "bidirectional"))
      (node (ref "IC18") (pin "3") (pinfunction "GND_3") (pintype "bidirectional"))
      (node (ref "IC18") (pin "8") (pinfunction "A_8") (pintype "bidirectional"))
      (node (ref "IC19") (pin "3") (pinfunction "GND_3") (pintype "bidirectional"))
      (node (ref "IC19") (pin "8") (pinfunction "A_8") (pintype "bidirectional"))
      (node (ref "IC2") (pin "2") (pinfunction "GND_2") (pintype "bidirectional"))
      (node (ref "IC20") (pin "3") (pinfunction "GND_3") (pintype "bidirectional"))
      (node (ref "IC20") (pin "8") (pinfunction "A_8") (pintype "bidirectional"))
      (node (ref "IC21") (pin "10") (pinfunction "S3B_10") (pintype "bidirectional"))
      (node (ref "IC21") (pin "13") (pinfunction "S4B_13") (pintype "bidirectional"))
      (node (ref "IC21") (pin "8") (pinfunction "GND_8") (pintype "bidirectional"))
      (node (ref "IC22") (pin "P$3") (pinfunction "RGND_P$3") (pintype "bidirectional"))
      (node (ref "IC22") (pin "P$6") (pinfunction "GND_P$6") (pintype "bidirectional"))
      (node (ref "IC23") (pin "3") (pinfunction "GND_3") (pintype "bidirectional"))
      (node (ref "IC24") (pin "P$3") (pinfunction "RGND_P$3") (pintype "bidirectional"))
      (node (ref "IC24") (pin "P$6") (pinfunction "GND_P$6") (pintype "bidirectional"))
      (node (ref "IC3") (pin "2") (pinfunction "GND_2") (pintype "bidirectional"))
      (node (ref "IC4") (pin "2") (pinfunction "GND_2") (pintype "bidirectional"))
      (node (ref "IC5") (pin "2") (pinfunction "GND_2") (pintype "bidirectional"))
      (node (ref "IC6") (pin "2") (pinfunction "GND_2") (pintype "bidirectional"))
      (node (ref "IC7") (pin "2") (pinfunction "GND_2") (pintype "bidirectional"))
      (node (ref "IC8") (pin "2") (pinfunction "GND_2") (pintype "bidirectional"))
      (node (ref "IC9") (pin "2") (pinfunction "GND_2") (pintype "passive"))
      (node (ref "IC9") (pin "4") (pinfunction "GND_4") (pintype "passive"))
      (node (ref "J1") (pin "B10") (pinfunction "B10_B10") (pintype "bidirectional"))
      (node (ref "J1") (pin "B11") (pinfunction "B11_B11") (pintype "bidirectional"))
      (node (ref "J1") (pin "B12") (pinfunction "B12_B12") (pintype "bidirectional"))
      (node (ref "J1") (pin "B13") (pinfunction "B13_B13") (pintype "bidirectional"))
      (node (ref "J1") (pin "B14") (pinfunction "B14_B14") (pintype "bidirectional"))
      (node (ref "J1") (pin "B15") (pinfunction "B15_B15") (pintype "bidirectional"))
      (node (ref "J1") (pin "B16") (pinfunction "B16_B16") (pintype "bidirectional"))
      (node (ref "J1") (pin "B17") (pinfunction "B17_B17") (pintype "bidirectional"))
      (node (ref "J1") (pin "B18") (pinfunction "B18_B18") (pintype "bidirectional"))
      (node (ref "J1") (pin "B19") (pinfunction "B19_B19") (pintype "bidirectional"))
      (node (ref "J1") (pin "B2") (pinfunction "B2_B2") (pintype "bidirectional"))
      (node (ref "J1") (pin "B20") (pinfunction "B20_B20") (pintype "bidirectional"))
      (node (ref "J1") (pin "B21") (pinfunction "B21_B21") (pintype "bidirectional"))
      (node (ref "J1") (pin "B22") (pinfunction "B22_B22") (pintype "bidirectional"))
      (node (ref "J1") (pin "B23") (pinfunction "B23_B23") (pintype "bidirectional"))
      (node (ref "J1") (pin "B24") (pinfunction "B24_B24") (pintype "bidirectional"))
      (node (ref "J1") (pin "B25") (pinfunction "B25_B25") (pintype "bidirectional"))
      (node (ref "J1") (pin "B26") (pinfunction "B26_B26") (pintype "bidirectional"))
      (node (ref "J1") (pin "B27") (pinfunction "B27_B27") (pintype "bidirectional"))
      (node (ref "J1") (pin "B28") (pinfunction "B28_B28") (pintype "bidirectional"))
      (node (ref "J1") (pin "B29") (pinfunction "B29_B29") (pintype "bidirectional"))
      (node (ref "J1") (pin "B30") (pinfunction "B30_B30") (pintype "bidirectional"))
      (node (ref "J1") (pin "B31") (pinfunction "B31_B31") (pintype "bidirectional"))
      (node (ref "J1") (pin "B32") (pinfunction "B32_B32") (pintype "bidirectional"))
      (node (ref "J1") (pin "B33") (pinfunction "B33_B33") (pintype "bidirectional"))
      (node (ref "J1") (pin "B34") (pinfunction "B34_B34") (pintype "bidirectional"))
      (node (ref "J1") (pin "B35") (pinfunction "B35_B35") (pintype "bidirectional"))
      (node (ref "J1") (pin "B36") (pinfunction "B36_B36") (pintype "bidirectional"))
      (node (ref "J1") (pin "B37") (pinfunction "B37_B37") (pintype "bidirectional"))
      (node (ref "J1") (pin "B38") (pinfunction "B38_B38") (pintype "bidirectional"))
      (node (ref "J1") (pin "B39") (pinfunction "B39_B39") (pintype "bidirectional"))
      (node (ref "J1") (pin "B40") (pinfunction "B40_B40") (pintype "bidirectional"))
      (node (ref "J1") (pin "B41") (pinfunction "B41_B41") (pintype "bidirectional"))
      (node (ref "J1") (pin "B42") (pinfunction "B42_B42") (pintype "bidirectional"))
      (node (ref "J1") (pin "B43") (pinfunction "B43_B43") (pintype "bidirectional"))
      (node (ref "J1") (pin "B44") (pinfunction "B44_B44") (pintype "bidirectional"))
      (node (ref "J1") (pin "B45") (pinfunction "B45_B45") (pintype "bidirectional"))
      (node (ref "J1") (pin "B47") (pinfunction "B47_B47") (pintype "bidirectional"))
      (node (ref "J1") (pin "B5") (pinfunction "B5_B5") (pintype "bidirectional"))
      (node (ref "J1") (pin "B6") (pinfunction "B6_B6") (pintype "bidirectional"))
      (node (ref "J1") (pin "B7") (pinfunction "B7_B7") (pintype "bidirectional"))
      (node (ref "J1") (pin "B8") (pinfunction "B8_B8") (pintype "bidirectional"))
      (node (ref "J1") (pin "B9") (pinfunction "B9_B9") (pintype "bidirectional"))
      (node (ref "JP13") (pin "1") (pinfunction "1_1") (pintype "passive"))
      (node (ref "JP17") (pin "3") (pinfunction "P$3_3") (pintype "bidirectional"))
      (node (ref "JP2") (pin "1") (pinfunction "1_1") (pintype "passive"))
      (node (ref "R15") (pin "1") (pinfunction "1_1") (pintype "passive"))
      (node (ref "R17") (pin "1") (pinfunction "1_1") (pintype "passive"))
      (node (ref "R19") (pin "1") (pinfunction "1_1") (pintype "passive"))
      (node (ref "R21") (pin "1") (pinfunction "1_1") (pintype "passive"))
      (node (ref "R23") (pin "1") (pinfunction "1_1") (pintype "passive"))
      (node (ref "R25") (pin "1") (pinfunction "1_1") (pintype "passive"))
      (node (ref "R27") (pin "1") (pinfunction "1_1") (pintype "passive"))
      (node (ref "R29") (pin "1") (pinfunction "1_1") (pintype "passive"))
      (node (ref "R31") (pin "1") (pinfunction "1_1") (pintype "passive"))
      (node (ref "R33") (pin "1") (pinfunction "1_1") (pintype "passive"))
      (node (ref "R35") (pin "1") (pinfunction "1_1") (pintype "passive"))
      (node (ref "R37") (pin "1") (pinfunction "1_1") (pintype "passive"))
      (node (ref "R39") (pin "1") (pinfunction "1_1") (pintype "passive"))
      (node (ref "R4") (pin "3") (pinfunction "3_3") (pintype "passive"))
      (node (ref "R41") (pin "1") (pinfunction "1_1") (pintype "passive"))
      (node (ref "R43") (pin "1") (pinfunction "1_1") (pintype "passive"))
      (node (ref "R5") (pin "3") (pinfunction "3_3") (pintype "passive"))
      (node (ref "R6") (pin "3") (pinfunction "3_3") (pintype "passive"))
      (node (ref "R8") (pin "1") (pinfunction "1_1") (pintype "passive"))
      (node (ref "R9") (pin "1") (pinfunction "1_1") (pintype "passive"))
      (node (ref "TP18") (pin "TP") (pinfunction "TP_TP") (pintype "input"))
      (node (ref "TP31") (pin "TP") (pinfunction "TP_TP") (pintype "input"))
      (node (ref "TP32") (pin "TP") (pinfunction "TP_TP") (pintype "input"))
      (node (ref "TP33") (pin "TP") (pinfunction "TP_TP") (pintype "input"))
      (node (ref "TP34") (pin "TP") (pinfunction "TP_TP") (pintype "input"))
      (node (ref "TP35") (pin "TP") (pinfunction "TP_TP") (pintype "input"))
      (node (ref "TP36") (pin "TP") (pinfunction "TP_TP") (pintype "input"))
      (node (ref "TP38") (pin "TP") (pinfunction "TP_TP") (pintype "input"))
    )
    (net (code "43") (name "/HOLD") (class "Default")
      (node (ref "IC1") (pin "P$37") (pinfunction "HOLD_P$37") (pintype "bidirectional"))
      (node (ref "R38") (pin "1") (pinfunction "1_1") (pintype "passive"))
      (node (ref "R39") (pin "2") (pinfunction "2_2") (pintype "passive"))
    )
    (net (code "44") (name "/HOLD_T") (class "Default")
      (node (ref "J1") (pin "A25") (pinfunction "A25_A25") (pintype "bidirectional"))
      (node (ref "R38") (pin "2") (pinfunction "2_2") (pintype "passive"))
    )
    (net (code "45") (name "/MUX_DAC_EN") (class "Default")
      (node (ref "IC21") (pin "15") (pinfunction "~{EN}_15") (pintype "bidirectional"))
      (node (ref "J1") (pin "A22") (pinfunction "A22_A22") (pintype "bidirectional"))
    )
    (net (code "46") (name "/MUX_DAC_SEL") (class "Default")
      (node (ref "IC21") (pin "1") (pinfunction "IN_1") (pintype "bidirectional"))
      (node (ref "J1") (pin "A21") (pinfunction "A21_A21") (pintype "bidirectional"))
    )
    (net (code "47") (name "/MUX_REF_1") (class "Default")
      (node (ref "IC2") (pin "6") (pinfunction "IN_6") (pintype "bidirectional"))
      (node (ref "J1") (pin "A12") (pinfunction "A12_A12") (pintype "bidirectional"))
    )
    (net (code "48") (name "/MUX_REF_2") (class "Default")
      (node (ref "IC3") (pin "6") (pinfunction "IN_6") (pintype "bidirectional"))
      (node (ref "J1") (pin "A13") (pinfunction "A13_A13") (pintype "bidirectional"))
    )
    (net (code "49") (name "/MUX_REF_3") (class "Default")
      (node (ref "IC4") (pin "6") (pinfunction "IN_6") (pintype "bidirectional"))
      (node (ref "J1") (pin "A9") (pinfunction "A9_A9") (pintype "bidirectional"))
    )
    (net (code "50") (name "/OP_MODE") (class "Default")
      (node (ref "IC1") (pin "P$11") (pinfunction "OP_MODE_P$11") (pintype "bidirectional"))
      (node (ref "R26") (pin "1") (pinfunction "1_1") (pintype "passive"))
      (node (ref "R27") (pin "2") (pinfunction "2_2") (pintype "passive"))
    )
    (net (code "51") (name "/OP_MODE_T") (class "Default")
      (node (ref "J1") (pin "A37") (pinfunction "A37_A37") (pintype "bidirectional"))
      (node (ref "R26") (pin "2") (pinfunction "2_2") (pintype "passive"))
    )
    (net (code "52") (name "/OUT_S") (class "Default")
      (node (ref "IC1") (pin "P$35") (pinfunction "OUT_S_P$35") (pintype "bidirectional"))
      (node (ref "R32") (pin "1") (pinfunction "1_1") (pintype "passive"))
      (node (ref "R33") (pin "2") (pinfunction "2_2") (pintype "passive"))
    )
    (net (code "53") (name "/OUT_S_T") (class "Default")
      (node (ref "J1") (pin "A24") (pinfunction "A24_A24") (pintype "bidirectional"))
      (node (ref "R32") (pin "2") (pinfunction "2_2") (pintype "passive"))
    )
    (net (code "54") (name "/POT_R1") (class "Default")
      (node (ref "JP4") (pin "3") (pinfunction "3_3") (pintype "passive"))
      (node (ref "R1") (pin "2") (pinfunction "2_2") (pintype "passive"))
      (node (ref "R1") (pin "3") (pinfunction "3_3") (pintype "passive"))
      (node (ref "TP27") (pin "TP") (pinfunction "TP_TP") (pintype "input"))
    )
    (net (code "55") (name "/POT_R2") (class "Default")
      (node (ref "JP4") (pin "1") (pinfunction "1_1") (pintype "passive"))
      (node (ref "R2") (pin "1") (pinfunction "1_1") (pintype "passive"))
      (node (ref "R2") (pin "2") (pinfunction "2_2") (pintype "passive"))
      (node (ref "TP28") (pin "TP") (pinfunction "TP_TP") (pintype "input"))
    )
    (net (code "56") (name "/POT_R4") (class "Default")
      (node (ref "IC2") (pin "3") (pinfunction "A1_3") (pintype "bidirectional"))
      (node (ref "R4") (pin "2") (pinfunction "2_2") (pintype "passive"))
      (node (ref "TP24") (pin "TP") (pinfunction "TP_TP") (pintype "input"))
    )
    (net (code "57") (name "/POT_R5") (class "Default")
      (node (ref "IC3") (pin "3") (pinfunction "A1_3") (pintype "bidirectional"))
      (node (ref "R5") (pin "2") (pinfunction "2_2") (pintype "passive"))
      (node (ref "TP25") (pin "TP") (pinfunction "TP_TP") (pintype "input"))
    )
    (net (code "58") (name "/POT_R6") (class "Default")
      (node (ref "IC4") (pin "3") (pinfunction "A1_3") (pintype "bidirectional"))
      (node (ref "R6") (pin "2") (pinfunction "2_2") (pintype "passive"))
      (node (ref "TP26") (pin "TP") (pinfunction "TP_TP") (pintype "input"))
    )
    (net (code "59") (name "/REFIN_DAC") (class "Default")
      (node (ref "C28") (pin "1") (pinfunction "1_1") (pintype "passive"))
      (node (ref "IC23") (pin "10") (pinfunction "REFIN_10") (pintype "bidirectional"))
      (node (ref "IC8") (pin "5") (pinfunction "VOUT_5") (pintype "bidirectional"))
      (node (ref "TP15") (pin "TP") (pinfunction "TP_TP") (pintype "input"))
    )
    (net (code "60") (name "/REF_ADC") (class "Default")
      (node (ref "C31") (pin "1") (pinfunction "1_1") (pintype "passive"))
      (node (ref "IC17") (pin "5") (pinfunction "VOUT_5") (pintype "bidirectional"))
      (node (ref "JP24") (pin "1") (pinfunction "1_1") (pintype "passive"))
      (node (ref "JP25") (pin "1") (pinfunction "1_1") (pintype "passive"))
      (node (ref "TP17") (pin "TP") (pinfunction "TP_TP") (pintype "input"))
    )
    (net (code "61") (name "/RES_BIAS_EXT") (class "Default")
      (node (ref "IC1") (pin "P$6") (pinfunction "RES_BIAS_EXT_P$6") (pintype "bidirectional"))
      (node (ref "JP4") (pin "2") (pinfunction "2_2") (pintype "passive"))
    )
    (net (code "62") (name "/RST") (class "Default")
      (node (ref "IC1") (pin "P$38") (pinfunction "RST_P$38") (pintype "bidirectional"))
      (node (ref "R36") (pin "1") (pinfunction "1_1") (pintype "passive"))
      (node (ref "R37") (pin "2") (pinfunction "2_2") (pintype "passive"))
    )
    (net (code "63") (name "/RST_CSA") (class "Default")
      (node (ref "IC1") (pin "P$12") (pinfunction "RST_CSA_P$12") (pintype "bidirectional"))
      (node (ref "R28") (pin "1") (pinfunction "1_1") (pintype "passive"))
      (node (ref "R29") (pin "2") (pinfunction "2_2") (pintype "passive"))
    )
    (net (code "64") (name "/RST_CSA_T") (class "Default")
      (node (ref "J1") (pin "A35") (pinfunction "A35_A35") (pintype "bidirectional"))
      (node (ref "R28") (pin "2") (pinfunction "2_2") (pintype "passive"))
    )
    (net (code "65") (name "/RST_T") (class "Default")
      (node (ref "J1") (pin "A26") (pinfunction "A26_A26") (pintype "bidirectional"))
      (node (ref "R36") (pin "2") (pinfunction "2_2") (pintype "passive"))
    )
    (net (code "66") (name "/SDI_DAC") (class "Default")
      (node (ref "IC23") (pin "7") (pinfunction "DIN_7") (pintype "bidirectional"))
      (node (ref "J1") (pin "A15") (pinfunction "A15_A15") (pintype "bidirectional"))
    )
    (net (code "67") (name "/SDI_REF") (class "Default")
      (node (ref "IC18") (pin "5") (pinfunction "SDI_5") (pintype "bidirectional"))
      (node (ref "IC19") (pin "5") (pinfunction "SDI_5") (pintype "bidirectional"))
      (node (ref "IC20") (pin "5") (pinfunction "SDI_5") (pintype "bidirectional"))
      (node (ref "J1") (pin "A6") (pinfunction "A6_A6") (pintype "bidirectional"))
    )
    (net (code "68") (name "/SDO_ADC1") (class "Default")
      (node (ref "IC22") (pin "P$8") (pinfunction "DOUT_P$8") (pintype "bidirectional"))
      (node (ref "J1") (pin "A43") (pinfunction "A43_A43") (pintype "bidirectional"))
      (node (ref "R3") (pin "1") (pinfunction "1_1") (pintype "passive"))
    )
    (net (code "69") (name "/SDO_ADC2") (class "Default")
      (node (ref "IC24") (pin "P$8") (pinfunction "DOUT_P$8") (pintype "bidirectional"))
      (node (ref "J1") (pin "A18") (pinfunction "A18_A18") (pintype "bidirectional"))
      (node (ref "R7") (pin "1") (pinfunction "1_1") (pintype "passive"))
    )
    (net (code "70") (name "/SGN") (class "Default")
      (node (ref "IC1") (pin "P$39") (pinfunction "SGN_P$39") (pintype "bidirectional"))
      (node (ref "R34") (pin "1") (pinfunction "1_1") (pintype "passive"))
      (node (ref "R35") (pin "2") (pinfunction "2_2") (pintype "passive"))
    )
    (net (code "71") (name "/SGN_T") (class "Default")
      (node (ref "J1") (pin "A27") (pinfunction "A27_A27") (pintype "bidirectional"))
      (node (ref "R34") (pin "2") (pinfunction "2_2") (pintype "passive"))
    )
    (net (code "72") (name "/V0NDAC") (class "Default")
      (node (ref "C59") (pin "1") (pinfunction "1_1") (pintype "passive"))
      (node (ref "IC21") (pin "5") (pinfunction "S2A_5") (pintype "bidirectional"))
      (node (ref "IC23") (pin "2") (pinfunction "VOUTB_2") (pintype "bidirectional"))
    )
    (net (code "73") (name "/V0PDAC") (class "Default")
      (node (ref "C60") (pin "1") (pinfunction "1_1") (pintype "passive"))
      (node (ref "IC21") (pin "2") (pinfunction "S1A_2") (pintype "bidirectional"))
      (node (ref "IC23") (pin "1") (pinfunction "VOUTA_1") (pintype "bidirectional"))
    )
    (net (code "74") (name "/V1NDAC") (class "Default")
      (node (ref "C53") (pin "1") (pinfunction "1_1") (pintype "passive"))
      (node (ref "IC21") (pin "14") (pinfunction "S4A_14") (pintype "bidirectional"))
      (node (ref "IC23") (pin "5") (pinfunction "VOUTD_5") (pintype "bidirectional"))
    )
    (net (code "75") (name "/V1PDAC") (class "Default")
      (node (ref "C52") (pin "1") (pinfunction "1_1") (pintype "passive"))
      (node (ref "IC21") (pin "11") (pinfunction "S3A_11") (pintype "bidirectional"))
      (node (ref "IC23") (pin "4") (pinfunction "VOUTC_4") (pintype "bidirectional"))
    )
    (net (code "76") (name "/VDD") (class "Default")
      (node (ref "C1") (pin "1") (pinfunction "1_1") (pintype "passive"))
      (node (ref "C2") (pin "1") (pinfunction "1_1") (pintype "passive"))
      (node (ref "C3") (pin "1") (pinfunction "1_1") (pintype "passive"))
      (node (ref "C39") (pin "2") (pinfunction "2_2") (pintype "passive"))
      (node (ref "C44") (pin "1") (pinfunction "1_1") (pintype "passive"))
      (node (ref "C58") (pin "2") (pinfunction "2_2") (pintype "passive"))
      (node (ref "IC11") (pin "3") (pinfunction "VO_3") (pintype "passive"))
      (node (ref "IC18") (pin "2") (pinfunction "VDD_2") (pintype "bidirectional"))
      (node (ref "IC19") (pin "2") (pinfunction "VDD_2") (pintype "bidirectional"))
      (node (ref "IC2") (pin "5") (pinfunction "VCC_5") (pintype "bidirectional"))
      (node (ref "IC20") (pin "2") (pinfunction "VDD_2") (pintype "bidirectional"))
      (node (ref "IC21") (pin "16") (pinfunction "VDD_16") (pintype "bidirectional"))
      (node (ref "IC23") (pin "8") (pinfunction "VDD_8") (pintype "bidirectional"))
      (node (ref "IC3") (pin "5") (pinfunction "VCC_5") (pintype "bidirectional"))
      (node (ref "IC4") (pin "5") (pinfunction "VCC_5") (pintype "bidirectional"))
      (node (ref "IC5") (pin "1") (pinfunction "VIN_1") (pintype "bidirectional"))
      (node (ref "IC5") (pin "3") (pinfunction "EN_3") (pintype "bidirectional"))
      (node (ref "IC6") (pin "1") (pinfunction "VIN_1") (pintype "bidirectional"))
      (node (ref "IC6") (pin "3") (pinfunction "EN_3") (pintype "bidirectional"))
      (node (ref "IC7") (pin "1") (pinfunction "VIN_1") (pintype "bidirectional"))
      (node (ref "IC7") (pin "3") (pinfunction "EN_3") (pintype "bidirectional"))
      (node (ref "TP5") (pin "TP") (pinfunction "TP_TP") (pintype "input"))
    )
    (net (code "77") (name "/VDD2") (class "Default")
      (node (ref "C46") (pin "1") (pinfunction "1_1") (pintype "passive"))
      (node (ref "C5") (pin "1") (pinfunction "1_1") (pintype "passive"))
      (node (ref "C7") (pin "1") (pinfunction "1_1") (pintype "passive"))
      (node (ref "IC10") (pin "1") (pinfunction "VIN_1") (pintype "bidirectional"))
      (node (ref "IC10") (pin "3") (pinfunction "EN_3") (pintype "bidirectional"))
      (node (ref "IC13") (pin "1") (pinfunction "VIN_1") (pintype "bidirectional"))
      (node (ref "IC13") (pin "3") (pinfunction "EN_3") (pintype "bidirectional"))
      (node (ref "IC9") (pin "3") (pinfunction "VO_3") (pintype "passive"))
      (node (ref "TP6") (pin "TP") (pinfunction "TP_TP") (pintype "input"))
    )
    (net (code "78") (name "/VDD3") (class "Default")
      (node (ref "C15") (pin "1") (pinfunction "1_1") (pintype "passive"))
      (node (ref "C16") (pin "1") (pinfunction "1_1") (pintype "passive"))
      (node (ref "C19") (pin "1") (pinfunction "1_1") (pintype "passive"))
      (node (ref "C20") (pin "1") (pinfunction "1_1") (pintype "passive"))
      (node (ref "C25") (pin "1") (pinfunction "1_1") (pintype "passive"))
      (node (ref "C30") (pin "1") (pinfunction "1_1") (pintype "passive"))
      (node (ref "C4") (pin "1") (pinfunction "1_1") (pintype "passive"))
      (node (ref "C51") (pin "1") (pinfunction "1_1") (pintype "passive"))
      (node (ref "IC12") (pin "8") (pinfunction "V+_8") (pintype "bidirectional"))
      (node (ref "IC14") (pin "8") (pinfunction "V+_8") (pintype "bidirectional"))
      (node (ref "IC15") (pin "3") (pinfunction "VO_3") (pintype "passive"))
      (node (ref "IC16") (pin "1") (pinfunction "VIN_1") (pintype "bidirectional"))
      (node (ref "IC16") (pin "3") (pinfunction "EN_3") (pintype "bidirectional"))
      (node (ref "IC17") (pin "1") (pinfunction "VIN_1") (pintype "bidirectional"))
      (node (ref "IC17") (pin "3") (pinfunction "EN_3") (pintype "bidirectional"))
      (node (ref "IC22") (pin "P$4") (pinfunction "VDD_P$4") (pintype "bidirectional"))
      (node (ref "IC24") (pin "P$4") (pinfunction "VDD_P$4") (pintype "bidirectional"))
      (node (ref "IC8") (pin "1") (pinfunction "VIN_1") (pintype "bidirectional"))
      (node (ref "IC8") (pin "3") (pinfunction "EN_3") (pintype "bidirectional"))
      (node (ref "TP45") (pin "TP") (pinfunction "TP_TP") (pintype "input"))
    )
    (net (code "79") (name "/VDD_REF_1") (class "Default")
      (node (ref "C26") (pin "1") (pinfunction "1_1") (pintype "passive"))
      (node (ref "IC18") (pin "7") (pinfunction "B_7") (pintype "bidirectional"))
      (node (ref "IC5") (pin "5") (pinfunction "VOUT_5") (pintype "bidirectional"))
      (node (ref "R4") (pin "1") (pinfunction "1_1") (pintype "passive"))
      (node (ref "TP41") (pin "TP") (pinfunction "TP_TP") (pintype "input"))
    )
    (net (code "80") (name "/VDD_REF_2") (class "Default")
      (node (ref "C27") (pin "1") (pinfunction "1_1") (pintype "passive"))
      (node (ref "IC19") (pin "7") (pinfunction "B_7") (pintype "bidirectional"))
      (node (ref "IC6") (pin "5") (pinfunction "VOUT_5") (pintype "bidirectional"))
      (node (ref "R5") (pin "1") (pinfunction "1_1") (pintype "passive"))
      (node (ref "TP42") (pin "TP") (pinfunction "TP_TP") (pintype "input"))
    )
    (net (code "81") (name "/VDD_REF_3") (class "Default")
      (node (ref "C35") (pin "1") (pinfunction "1_1") (pintype "passive"))
      (node (ref "IC20") (pin "7") (pinfunction "B_7") (pintype "bidirectional"))
      (node (ref "IC7") (pin "5") (pinfunction "VOUT_5") (pintype "bidirectional"))
      (node (ref "R6") (pin "1") (pinfunction "1_1") (pintype "passive"))
      (node (ref "TP43") (pin "TP") (pinfunction "TP_TP") (pintype "input"))
    )
    (net (code "82") (name "/VDD_SUPPLY_1") (class "Default")
      (node (ref "C43") (pin "1") (pinfunction "1_1") (pintype "passive"))
      (node (ref "IC11") (pin "1") (pinfunction "VI_1") (pintype "input"))
      (node (ref "JP5") (pin "1") (pinfunction "1_1") (pintype "passive"))
      (node (ref "TP1") (pin "TP") (pinfunction "TP_TP") (pintype "input"))
    )
    (net (code "83") (name "/VDD_SUPPLY_2") (class "Default")
      (node (ref "C45") (pin "1") (pinfunction "1_1") (pintype "passive"))
      (node (ref "IC9") (pin "1") (pinfunction "VI_1") (pintype "input"))
      (node (ref "JP8") (pin "1") (pinfunction "1_1") (pintype "passive"))
      (node (ref "TP3") (pin "TP") (pinfunction "TP_TP") (pintype "input"))
    )
    (net (code "84") (name "/VDD_SUPPLY_3") (class "Default")
      (node (ref "C50") (pin "1") (pinfunction "1_1") (pintype "passive"))
      (node (ref "IC15") (pin "1") (pinfunction "VI_1") (pintype "input"))
      (node (ref "JP20") (pin "1") (pinfunction "1_1") (pintype "passive"))
      (node (ref "TP44") (pin "TP") (pinfunction "TP_TP") (pintype "input"))
    )
    (net (code "85") (name "/VDD_SUPPLY_IN_1") (class "Default")
      (node (ref "JP17") (pin "1") (pinfunction "P$1_1") (pintype "bidirectional"))
      (node (ref "JP20") (pin "2") (pinfunction "2_2") (pintype "passive"))
      (node (ref "JP5") (pin "2") (pinfunction "2_2") (pintype "passive"))
      (node (ref "TP2") (pin "TP") (pinfunction "TP_TP") (pintype "input"))
    )
    (net (code "86") (name "/VDD_SUPPLY_IN_2") (class "Default")
      (node (ref "JP17") (pin "2") (pinfunction "P$2_2") (pintype "bidirectional"))
      (node (ref "JP8") (pin "2") (pinfunction "2_2") (pintype "passive"))
      (node (ref "TP4") (pin "TP") (pinfunction "TP_TP") (pintype "input"))
    )
    (net (code "87") (name "/VI+_FIL") (class "Default")
      (node (ref "IC1") (pin "P$22") (pinfunction "VI+_FIL_P$22") (pintype "input"))
      (node (ref "JP11") (pin "2") (pinfunction "2_2") (pintype "passive"))
    )
    (net (code "88") (name "/VI+_FIL_DAC") (class "Default")
      (node (ref "C54") (pin "1") (pinfunction "1_1") (pintype "passive"))
      (node (ref "IC21") (pin "4") (pinfunction "D1_4") (pintype "bidirectional"))
      (node (ref "JP11") (pin "1") (pinfunction "1_1") (pintype "passive"))
    )
    (net (code "89") (name "/VI-_FIL") (class "Default")
      (node (ref "IC1") (pin "P$23") (pinfunction "VI-_FIL_P$23") (pintype "input"))
      (node (ref "JP12") (pin "2") (pinfunction "2_2") (pintype "passive"))
    )
    (net (code "90") (name "/VI-_FIL_DAC") (class "Default")
      (node (ref "C55") (pin "1") (pinfunction "1_1") (pintype "passive"))
      (node (ref "IC21") (pin "7") (pinfunction "D2_7") (pintype "bidirectional"))
      (node (ref "JP12") (pin "1") (pinfunction "1_1") (pintype "passive"))
    )
    (net (code "91") (name "/VICM") (class "Default")
      (node (ref "IC1") (pin "P$40") (pinfunction "VICM_P$40") (pintype "input"))
      (node (ref "IC21") (pin "3") (pinfunction "S1B_3") (pintype "bidirectional"))
      (node (ref "IC21") (pin "6") (pinfunction "S2B_6") (pintype "bidirectional"))
      (node (ref "JP15") (pin "2") (pinfunction "2_2") (pintype "passive"))
      (node (ref "TP12") (pin "TP") (pinfunction "TP_TP") (pintype "input"))
    )
    (net (code "92") (name "/VICM_BUFF") (class "Default")
      (node (ref "IC12") (pin "1") (pinfunction "OUTA_1") (pintype "bidirectional"))
      (node (ref "IC12") (pin "2") (pinfunction "-INA_2") (pintype "bidirectional"))
      (node (ref "R11") (pin "2") (pinfunction "2_2") (pintype "passive"))
    )
    (net (code "93") (name "/VICM_BUFF_FIL") (class "Default")
      (node (ref "C32") (pin "1") (pinfunction "1_1") (pintype "passive"))
      (node (ref "JP15") (pin "1") (pinfunction "1_1") (pintype "passive"))
      (node (ref "R11") (pin "1") (pinfunction "1_1") (pintype "passive"))
    )
    (net (code "94") (name "/VICM_MUX") (class "Default")
      (node (ref "C47") (pin "1") (pinfunction "1_1") (pintype "passive"))
      (node (ref "IC12") (pin "3") (pinfunction "+INA_3") (pintype "bidirectional"))
      (node (ref "IC3") (pin "4") (pinfunction "B_4") (pintype "bidirectional"))
      (node (ref "JP15") (pin "3") (pinfunction "3_3") (pintype "passive"))
      (node (ref "TP11") (pin "TP") (pinfunction "TP_TP") (pintype "input"))
    )
    (net (code "95") (name "/VIN_CSA") (class "Default")
      (node (ref "IC1") (pin "P$15") (pinfunction "VIN_CSA_P$15") (pintype "input"))
      (node (ref "JP1") (pin "3") (pinfunction "3_3") (pintype "passive"))
      (node (ref "JP10") (pin "2") (pinfunction "2_2") (pintype "passive"))
    )
    (net (code "96") (name "/VIN_CSA_1") (class "Default")
      (node (ref "C36") (pin "1") (pinfunction "1_1") (pintype "passive"))
      (node (ref "C56") (pin "1") (pinfunction "1_1") (pintype "passive"))
      (node (ref "IC21") (pin "9") (pinfunction "D3_9") (pintype "bidirectional"))
      (node (ref "JP9") (pin "1") (pinfunction "1_1") (pintype "passive"))
    )
    (net (code "97") (name "/VL_ADC") (class "Default")
      (node (ref "C14") (pin "1") (pinfunction "1_1") (pintype "passive"))
      (node (ref "C21") (pin "1") (pinfunction "1_1") (pintype "passive"))
      (node (ref "C22") (pin "1") (pinfunction "1_1") (pintype "passive"))
      (node (ref "C29") (pin "1") (pinfunction "1_1") (pintype "passive"))
      (node (ref "C8") (pin "1") (pinfunction "1_1") (pintype "passive"))
      (node (ref "IC16") (pin "5") (pinfunction "VOUT_5") (pintype "bidirectional"))
      (node (ref "IC22") (pin "P$7") (pinfunction "VL_P$7") (pintype "bidirectional"))
      (node (ref "IC24") (pin "P$7") (pinfunction "VL_P$7") (pintype "bidirectional"))
      (node (ref "R3") (pin "2") (pinfunction "2_2") (pintype "passive"))
      (node (ref "R7") (pin "2") (pinfunction "2_2") (pintype "passive"))
      (node (ref "TP16") (pin "TP") (pinfunction "TP_TP") (pintype "input"))
    )
    (net (code "98") (name "/VO+_BP_FIL") (class "Default")
      (node (ref "IC1") (pin "P$24") (pinfunction "VO+_BP_FIL_P$24") (pintype "output"))
      (node (ref "JP3") (pin "3") (pinfunction "3_3") (pintype "passive"))
    )
    (net (code "99") (name "/VO+_CH") (class "Default")
      (node (ref "IC1") (pin "P$50") (pinfunction "VO+_CH_P$50") (pintype "input"))
      (node (ref "JP14") (pin "3") (pinfunction "3_3") (pintype "passive"))
    )
    (net (code "100") (name "/VO+_FIL") (class "Default")
      (node (ref "IC1") (pin "P$30") (pinfunction "VO+_FIL_P$30") (pintype "output"))
      (node (ref "JP3") (pin "1") (pinfunction "1_1") (pintype "passive"))
    )
    (net (code "101") (name "/VO-_BP_FIL") (class "Default")
      (node (ref "IC1") (pin "P$25") (pinfunction "VO-_BP_FIL_P$25") (pintype "output"))
      (node (ref "JP18") (pin "3") (pinfunction "3_3") (pintype "passive"))
    )
    (net (code "102") (name "/VO-_CH") (class "Default")
      (node (ref "IC1") (pin "P$52") (pinfunction "VO-_CH_P$52") (pintype "input"))
      (node (ref "JP13") (pin "3") (pinfunction "3_3") (pintype "passive"))
    )
    (net (code "103") (name "/VO-_FIL") (class "Default")
      (node (ref "IC1") (pin "P$31") (pinfunction "VO-_FIL_P$31") (pintype "output"))
      (node (ref "JP18") (pin "1") (pinfunction "1_1") (pintype "passive"))
    )
    (net (code "104") (name "/VOCM") (class "Default")
      (node (ref "IC1") (pin "P$34") (pinfunction "VOCM_AUX_P$34") (pintype "input"))
      (node (ref "IC1") (pin "P$36") (pinfunction "VOCM_P$36") (pintype "input"))
      (node (ref "JP16") (pin "2") (pinfunction "2_2") (pintype "passive"))
      (node (ref "TP14") (pin "TP") (pinfunction "TP_TP") (pintype "input"))
    )
    (net (code "105") (name "/VOCM_1") (class "Default")
      (node (ref "C49") (pin "1") (pinfunction "1_1") (pintype "passive"))
      (node (ref "IC14") (pin "3") (pinfunction "+INA_3") (pintype "bidirectional"))
      (node (ref "IC2") (pin "4") (pinfunction "B_4") (pintype "bidirectional"))
      (node (ref "JP7") (pin "3") (pinfunction "3_3") (pintype "passive"))
      (node (ref "TP30") (pin "TP") (pinfunction "TP_TP") (pintype "input"))
    )
    (net (code "106") (name "/VOCM_BUFF") (class "Default")
      (node (ref "IC12") (pin "6") (pinfunction "-INB_6") (pintype "bidirectional"))
      (node (ref "IC12") (pin "7") (pinfunction "OUTB_7") (pintype "bidirectional"))
      (node (ref "R10") (pin "2") (pinfunction "2_2") (pintype "passive"))
    )
    (net (code "107") (name "/VOCM_BUFF_FIL") (class "Default")
      (node (ref "C33") (pin "1") (pinfunction "1_1") (pintype "passive"))
      (node (ref "JP16") (pin "1") (pinfunction "1_1") (pintype "passive"))
      (node (ref "R10") (pin "1") (pinfunction "1_1") (pintype "passive"))
    )
    (net (code "108") (name "/VOCM_MUX") (class "Default")
      (node (ref "C48") (pin "1") (pinfunction "1_1") (pintype "passive"))
      (node (ref "IC12") (pin "5") (pinfunction "+INB_5") (pintype "bidirectional"))
      (node (ref "IC4") (pin "4") (pinfunction "B_4") (pintype "bidirectional"))
      (node (ref "JP16") (pin "3") (pinfunction "3_3") (pintype "passive"))
      (node (ref "TP13") (pin "TP") (pinfunction "TP_TP") (pintype "input"))
    )
    (net (code "109") (name "/VOUT_CSA") (class "Default")
      (node (ref "IC1") (pin "P$54") (pinfunction "VOUT_CSA_P$54") (pintype "output"))
      (node (ref "JP14") (pin "1") (pinfunction "1_1") (pintype "passive"))
      (node (ref "TP9") (pin "TP") (pinfunction "TP_TP") (pintype "input"))
    )
    (net (code "110") (name "/VREF_ADC1") (class "Default")
      (node (ref "C17") (pin "1") (pinfunction "1_1") (pintype "passive"))
      (node (ref "C18") (pin "1") (pinfunction "1_1") (pintype "passive"))
      (node (ref "IC22") (pin "P$2") (pinfunction "REF_P$2") (pintype "bidirectional"))
      (node (ref "JP24") (pin "2") (pinfunction "2_2") (pintype "passive"))
    )
    (net (code "111") (name "/VREF_ADC2") (class "Default")
      (node (ref "C23") (pin "1") (pinfunction "1_1") (pintype "passive"))
      (node (ref "C24") (pin "1") (pinfunction "1_1") (pintype "passive"))
      (node (ref "IC24") (pin "P$2") (pinfunction "REF_P$2") (pintype "bidirectional"))
      (node (ref "JP25") (pin "2") (pinfunction "2_2") (pintype "passive"))
    )
    (net (code "112") (name "/VSS") (class "Default")
      (node (ref "IC12") (pin "4") (pinfunction "V-_4") (pintype "bidirectional"))
      (node (ref "IC14") (pin "4") (pinfunction "V-_4") (pintype "bidirectional"))
      (node (ref "JP23") (pin "1") (pinfunction "1_1") (pintype "passive"))
    )
    (net (code "113") (name "/VSS_IN") (class "Default")
      (node (ref "JP17") (pin "4") (pinfunction "P$4_4") (pintype "bidirectional"))
      (node (ref "JP23") (pin "2") (pinfunction "2_2") (pintype "passive"))
      (node (ref "TP39") (pin "TP") (pinfunction "TP_TP") (pintype "input"))
    )
    (net (code "114") (name "/V_REF_PRECHAR") (class "Default")
      (node (ref "IC1") (pin "P$7") (pinfunction "V_REF_PRECHAR_P$7") (pintype "input"))
      (node (ref "JP7") (pin "2") (pinfunction "2_2") (pintype "passive"))
      (node (ref "TP37") (pin "TP") (pinfunction "TP_TP") (pintype "input"))
    )
    (net (code "115") (name "/V_REF_PRECHAR_BUFF") (class "Default")
      (node (ref "IC14") (pin "1") (pinfunction "OUTA_1") (pintype "bidirectional"))
      (node (ref "IC14") (pin "2") (pinfunction "-INA_2") (pintype "bidirectional"))
      (node (ref "R12") (pin "2") (pinfunction "2_2") (pintype "passive"))
    )
    (net (code "116") (name "/V_REF_PRECHAR_BUFF_FIL") (class "Default")
      (node (ref "C34") (pin "1") (pinfunction "1_1") (pintype "passive"))
      (node (ref "JP7") (pin "1") (pinfunction "1_1") (pintype "passive"))
      (node (ref "R12") (pin "1") (pinfunction "1_1") (pintype "passive"))
    )
    (net (code "117") (name "/~{CS_ADC1}") (class "Default")
      (node (ref "IC22") (pin "P$9") (pinfunction "CNVST_P$9") (pintype "bidirectional"))
      (node (ref "J1") (pin "A44") (pinfunction "A44_A44") (pintype "bidirectional"))
    )
    (net (code "118") (name "/~{CS_ADC2}") (class "Default")
      (node (ref "IC24") (pin "P$9") (pinfunction "CNVST_P$9") (pintype "bidirectional"))
      (node (ref "J1") (pin "A19") (pinfunction "A19_A19") (pintype "bidirectional"))
    )
    (net (code "119") (name "/~{CS_DAC}") (class "Default")
      (node (ref "IC23") (pin "9") (pinfunction "~{SYNC}_9") (pintype "bidirectional"))
      (node (ref "J1") (pin "A14") (pinfunction "A14_A14") (pintype "bidirectional"))
    )
    (net (code "120") (name "Net-(C36-Pad2)") (class "Default")
      (node (ref "C36") (pin "2") (pinfunction "2_2") (pintype "passive"))
      (node (ref "C37") (pin "1") (pinfunction "1_1") (pintype "passive"))
      (node (ref "JP9") (pin "2") (pinfunction "2_2") (pintype "passive"))
    )
    (net (code "121") (name "Net-(C37-Pad2)") (class "Default")
      (node (ref "C37") (pin "2") (pinfunction "2_2") (pintype "passive"))
      (node (ref "JP10") (pin "1") (pinfunction "1_1") (pintype "passive"))
    )
    (net (code "122") (name "Net-(C38-Pad1)") (class "Default")
      (node (ref "C38") (pin "1") (pinfunction "1_1") (pintype "passive"))
      (node (ref "JP1") (pin "2") (pinfunction "2_2") (pintype "passive"))
    )
    (net (code "123") (name "Net-(C42-Pad1)") (class "Default")
      (node (ref "C42") (pin "1") (pinfunction "1_1") (pintype "passive"))
      (node (ref "J1") (pin "B50") (pinfunction "B50_B50") (pintype "bidirectional"))
      (node (ref "R8") (pin "2") (pinfunction "2_2") (pintype "passive"))
    )
    (net (code "124") (name "Net-(J1-PadA46)") (class "Default")
      (node (ref "J1") (pin "A46") (pinfunction "A46_A46") (pintype "bidirectional"))
      (node (ref "J1") (pin "A48") (pinfunction "A48_A48") (pintype "bidirectional"))
    )
    (net (code "125") (name "Net-(J1-PadB1)") (class "Default")
      (node (ref "J1") (pin "B1") (pinfunction "B1_B1") (pintype "bidirectional"))
      (node (ref "R9") (pin "2") (pinfunction "2_2") (pintype "passive"))
    )
    (net (code "126") (name "unconnected-(IC5-NC-Pad4)") (class "Default")
      (node (ref "IC5") (pin "4") (pinfunction "NC_4") (pintype "bidirectional"))
    )
    (net (code "127") (name "unconnected-(IC6-NC-Pad4)") (class "Default")
      (node (ref "IC6") (pin "4") (pinfunction "NC_4") (pintype "bidirectional"))
    )
    (net (code "128") (name "unconnected-(IC7-NC-Pad4)") (class "Default")
      (node (ref "IC7") (pin "4") (pinfunction "NC_4") (pintype "bidirectional"))
    )
    (net (code "129") (name "unconnected-(IC8-NC-Pad4)") (class "Default")
      (node (ref "IC8") (pin "4") (pinfunction "NC_4") (pintype "bidirectional"))
    )
    (net (code "130") (name "unconnected-(IC10-NC-Pad4)") (class "Default")
      (node (ref "IC10") (pin "4") (pinfunction "NC_4") (pintype "bidirectional"))
    )
    (net (code "131") (name "unconnected-(IC13-NC-Pad4)") (class "Default")
      (node (ref "IC13") (pin "4") (pinfunction "NC_4") (pintype "bidirectional"))
    )
    (net (code "132") (name "unconnected-(IC14-+INB-Pad5)") (class "Default")
      (node (ref "IC14") (pin "5") (pinfunction "+INB_5") (pintype "bidirectional"))
    )
    (net (code "133") (name "unconnected-(IC14--INB-Pad6)") (class "Default")
      (node (ref "IC14") (pin "6") (pinfunction "-INB_6") (pintype "bidirectional"))
    )
    (net (code "134") (name "unconnected-(IC14-OUTB-Pad7)") (class "Default")
      (node (ref "IC14") (pin "7") (pinfunction "OUTB_7") (pintype "bidirectional"))
    )
    (net (code "135") (name "unconnected-(IC16-NC-Pad4)") (class "Default")
      (node (ref "IC16") (pin "4") (pinfunction "NC_4") (pintype "bidirectional"))
    )
    (net (code "136") (name "unconnected-(IC17-NC-Pad4)") (class "Default")
      (node (ref "IC17") (pin "4") (pinfunction "NC_4") (pintype "bidirectional"))
    )
    (net (code "137") (name "unconnected-(J1-PadA1)") (class "Default")
      (node (ref "J1") (pin "A1") (pinfunction "A1_A1") (pintype "bidirectional"))
    )
    (net (code "138") (name "unconnected-(J1-PadA2)") (class "Default")
      (node (ref "J1") (pin "A2") (pinfunction "A2_A2") (pintype "bidirectional"))
    )
    (net (code "139") (name "unconnected-(J1-PadA3)") (class "Default")
      (node (ref "J1") (pin "A3") (pinfunction "A3_A3") (pintype "bidirectional"))
    )
    (net (code "140") (name "unconnected-(J1-PadA4)") (class "Default")
      (node (ref "J1") (pin "A4") (pinfunction "A4_A4") (pintype "bidirectional"))
    )
    (net (code "141") (name "unconnected-(J1-PadA5)") (class "Default")
      (node (ref "J1") (pin "A5") (pinfunction "A5_A5") (pintype "bidirectional"))
    )
    (net (code "142") (name "unconnected-(J1-PadA17)") (class "Default")
      (node (ref "J1") (pin "A17") (pinfunction "A17_A17") (pintype "bidirectional"))
    )
    (net (code "143") (name "unconnected-(J1-PadA23)") (class "Default")
      (node (ref "J1") (pin "A23") (pinfunction "A23_A23") (pintype "bidirectional"))
    )
    (net (code "144") (name "unconnected-(J1-PadA29)") (class "Default")
      (node (ref "J1") (pin "A29") (pinfunction "A29_A29") (pintype "bidirectional"))
    )
    (net (code "145") (name "unconnected-(J1-PadA31)") (class "Default")
      (node (ref "J1") (pin "A31") (pinfunction "A31_A31") (pintype "bidirectional"))
    )
    (net (code "146") (name "unconnected-(J1-PadA39)") (class "Default")
      (node (ref "J1") (pin "A39") (pinfunction "A39_A39") (pintype "bidirectional"))
    )
    (net (code "147") (name "unconnected-(J1-PadA41)") (class "Default")
      (node (ref "J1") (pin "A41") (pinfunction "A41_A41") (pintype "bidirectional"))
    )
    (net (code "148") (name "unconnected-(J1-PadA47)") (class "Default")
      (node (ref "J1") (pin "A47") (pinfunction "A47_A47") (pintype "bidirectional"))
    )
    (net (code "149") (name "unconnected-(J1-PadA49)") (class "Default")
      (node (ref "J1") (pin "A49") (pinfunction "A49_A49") (pintype "bidirectional"))
    )
    (net (code "150") (name "unconnected-(J1-PadA50)") (class "Default")
      (node (ref "J1") (pin "A50") (pinfunction "A50_A50") (pintype "bidirectional"))
    )
    (net (code "151") (name "unconnected-(J1-PadB3)") (class "Default")
      (node (ref "J1") (pin "B3") (pinfunction "B3_B3") (pintype "bidirectional"))
    )
    (net (code "152") (name "unconnected-(J1-PadB4)") (class "Default")
      (node (ref "J1") (pin "B4") (pinfunction "B4_B4") (pintype "bidirectional"))
    )
    (net (code "153") (name "unconnected-(J1-PadB46)") (class "Default")
      (node (ref "J1") (pin "B46") (pinfunction "B46_B46") (pintype "bidirectional"))
    )
    (net (code "154") (name "unconnected-(J1-PadB48)") (class "Default")
      (node (ref "J1") (pin "B48") (pinfunction "B48_B48") (pintype "bidirectional"))
    )
    (net (code "155") (name "unconnected-(J1-PadB49)") (class "Default")
      (node (ref "J1") (pin "B49") (pinfunction "B49_B49") (pintype "bidirectional"))
    )
  )
)
